# qudong.net
KiCad netlist of a schematic drawn in Altium Designer
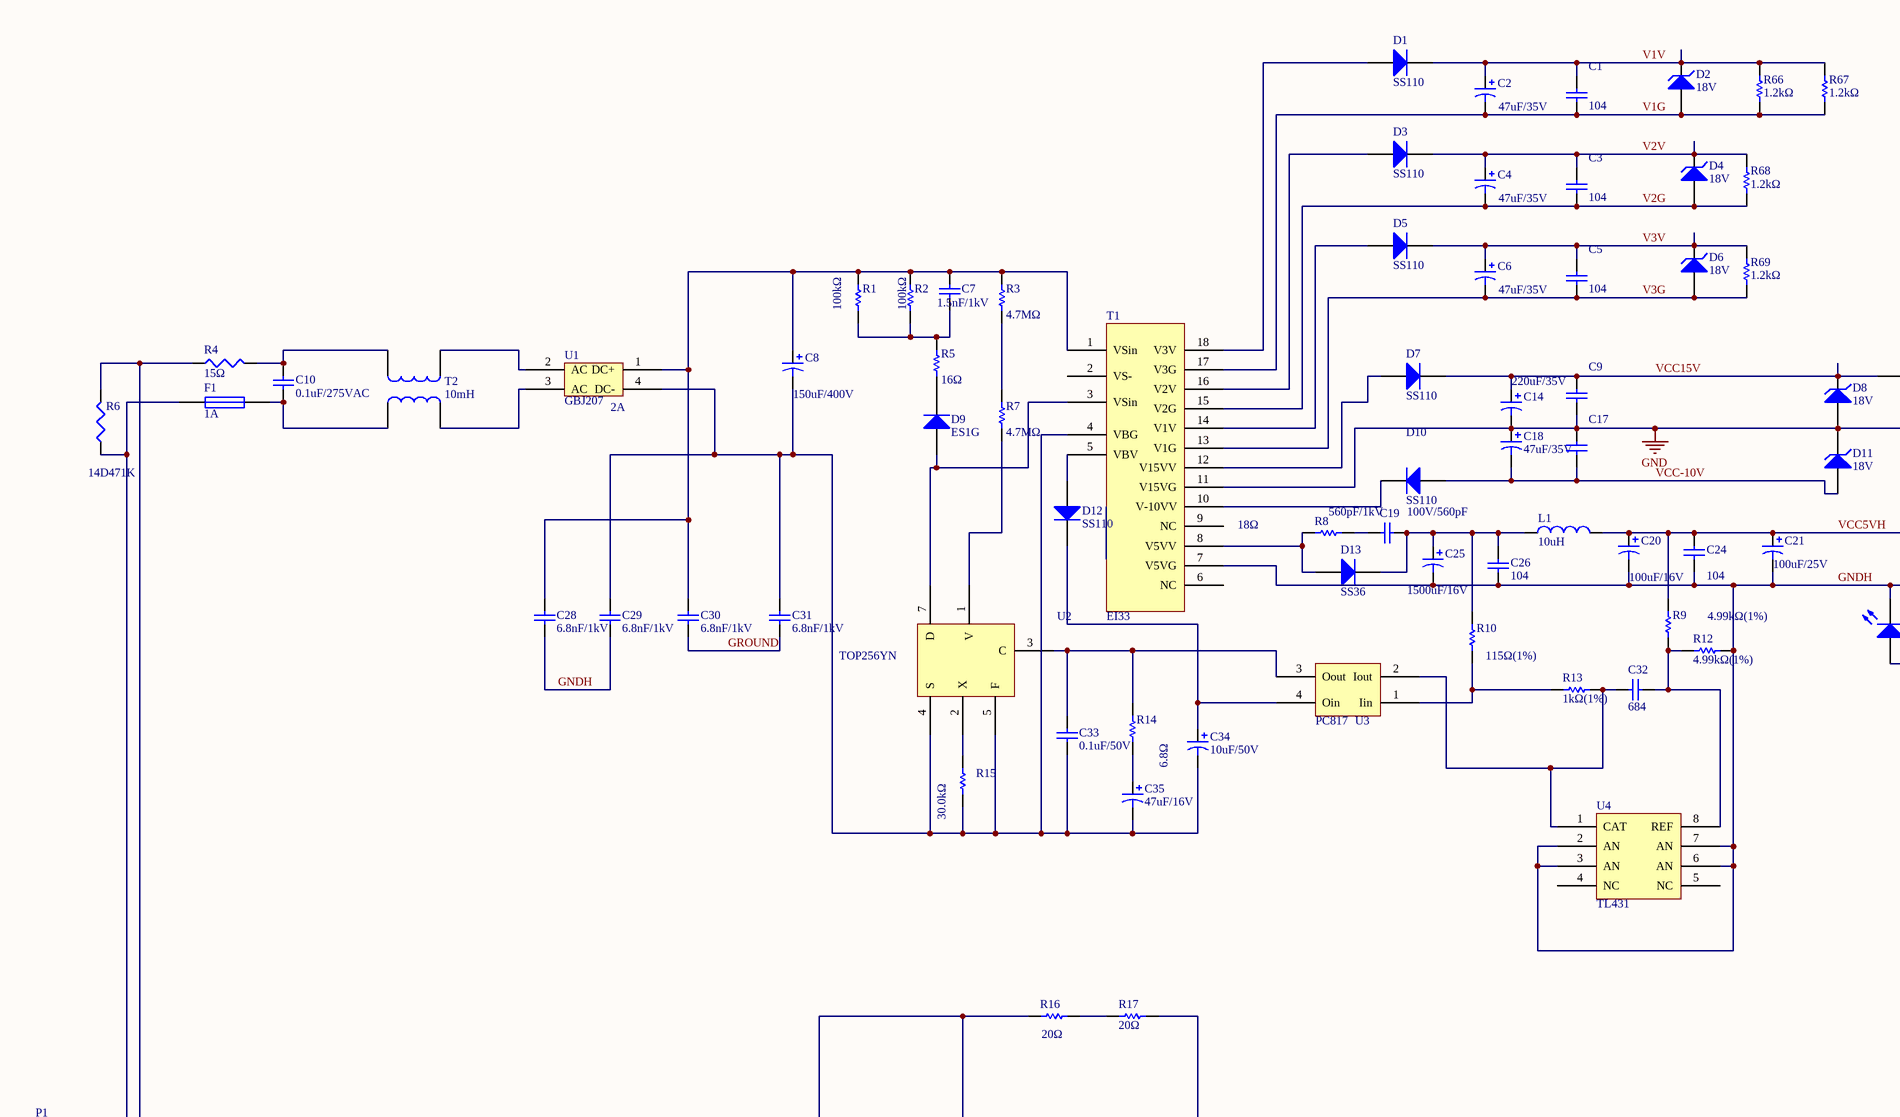
[diagram p0: qudong.SchDoc, top left]
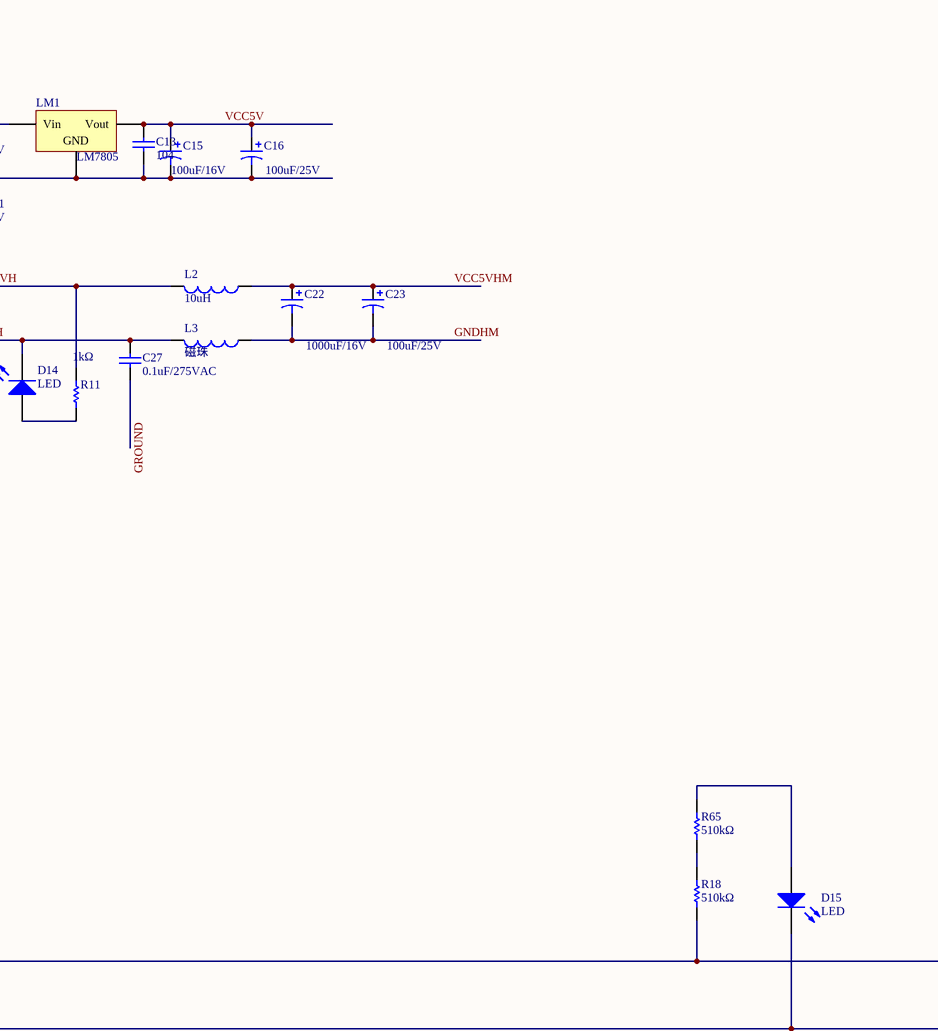
[diagram p1: qudong.SchDoc, top right]
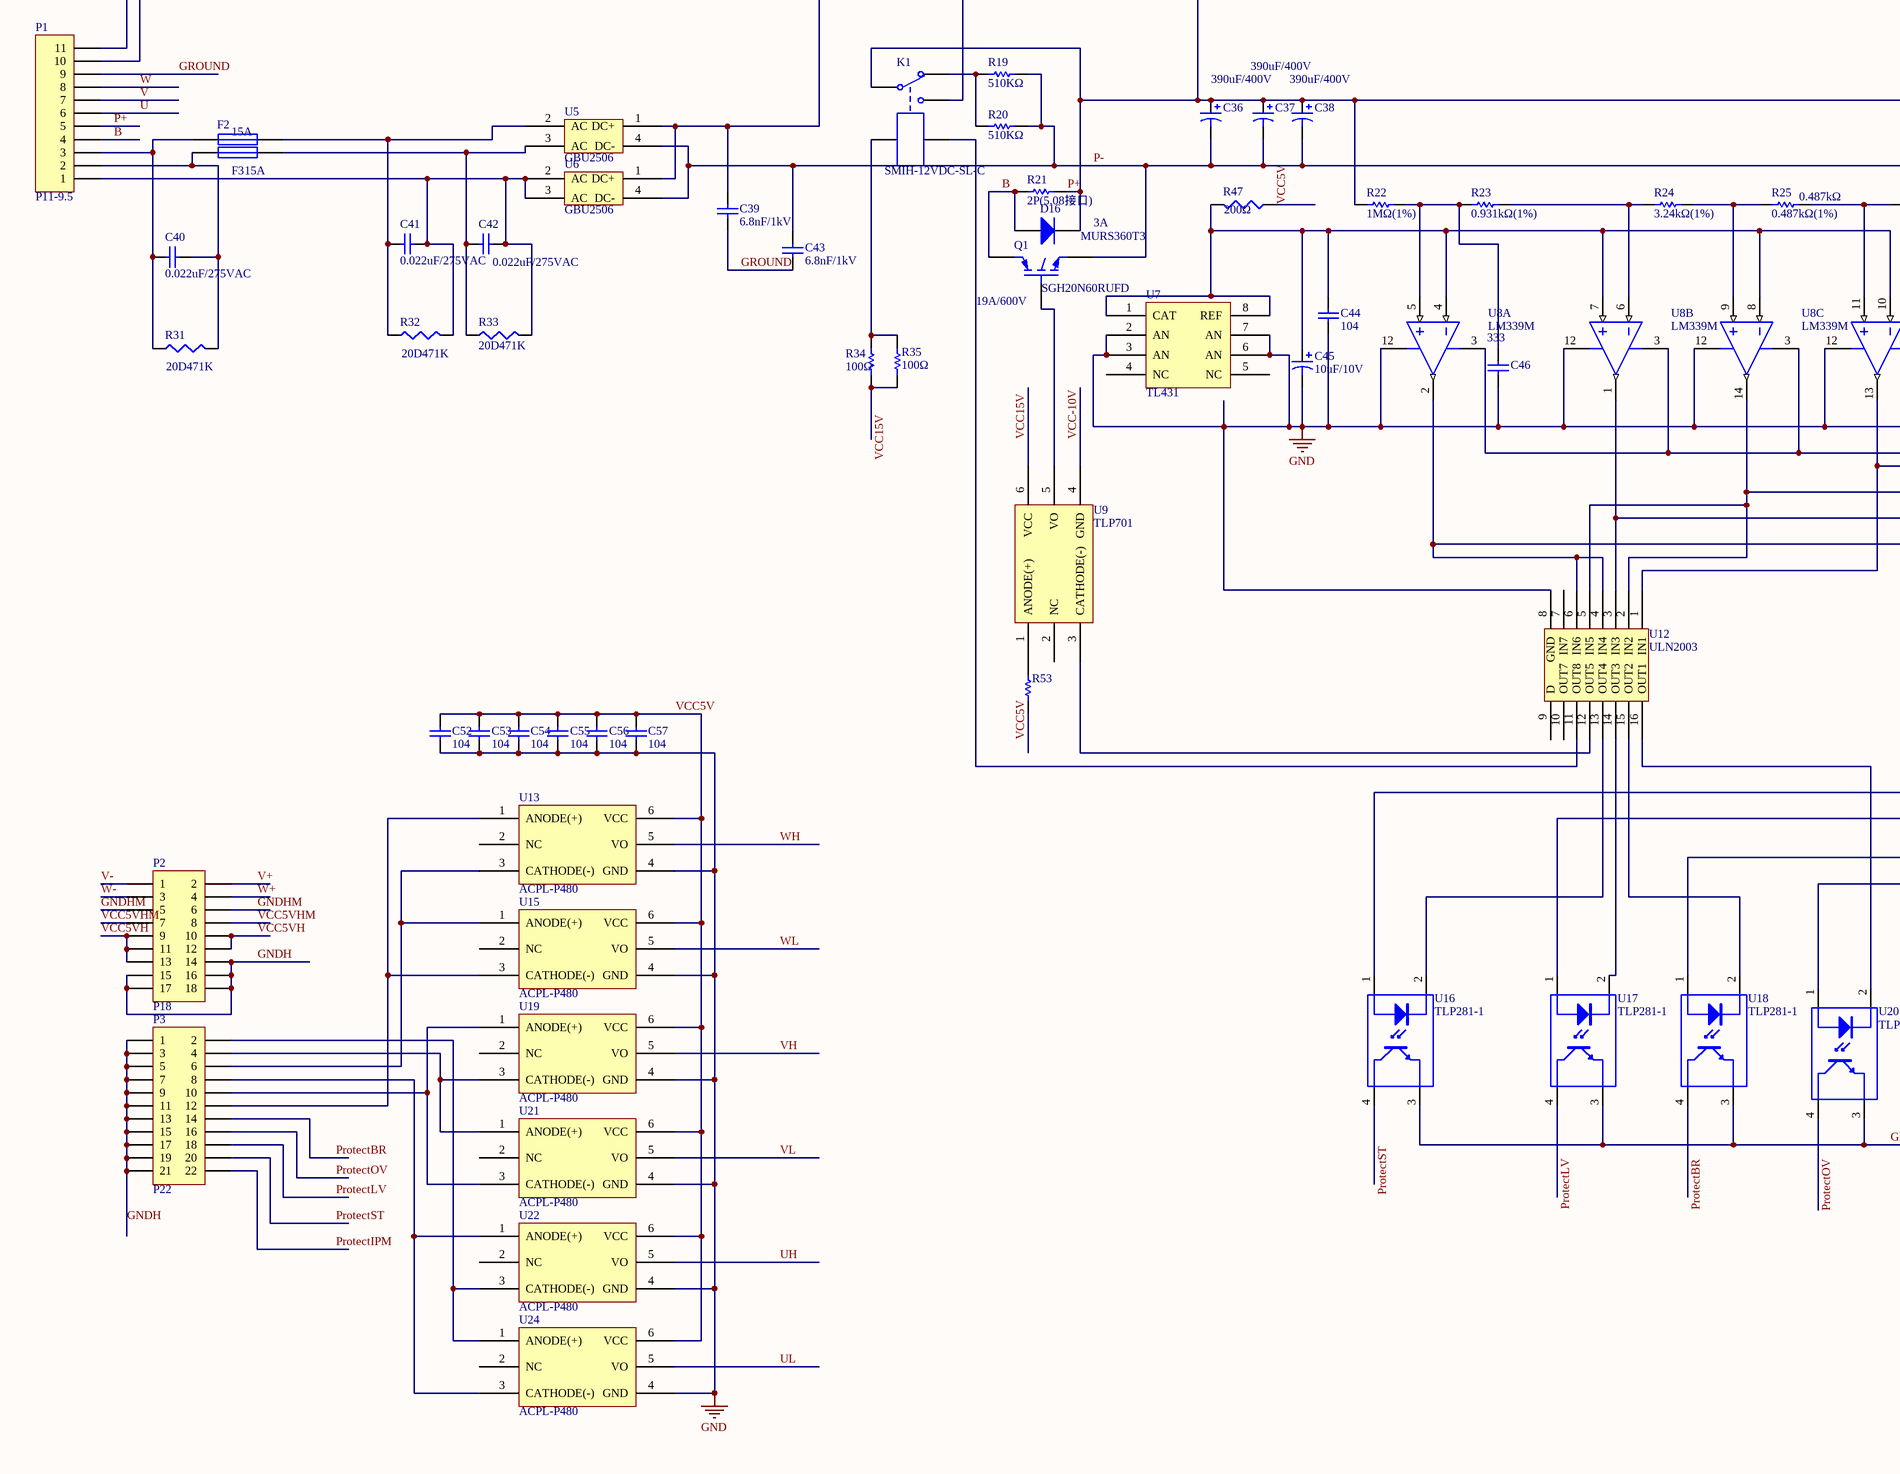
[diagram p2: qudong.SchDoc, bottom left]
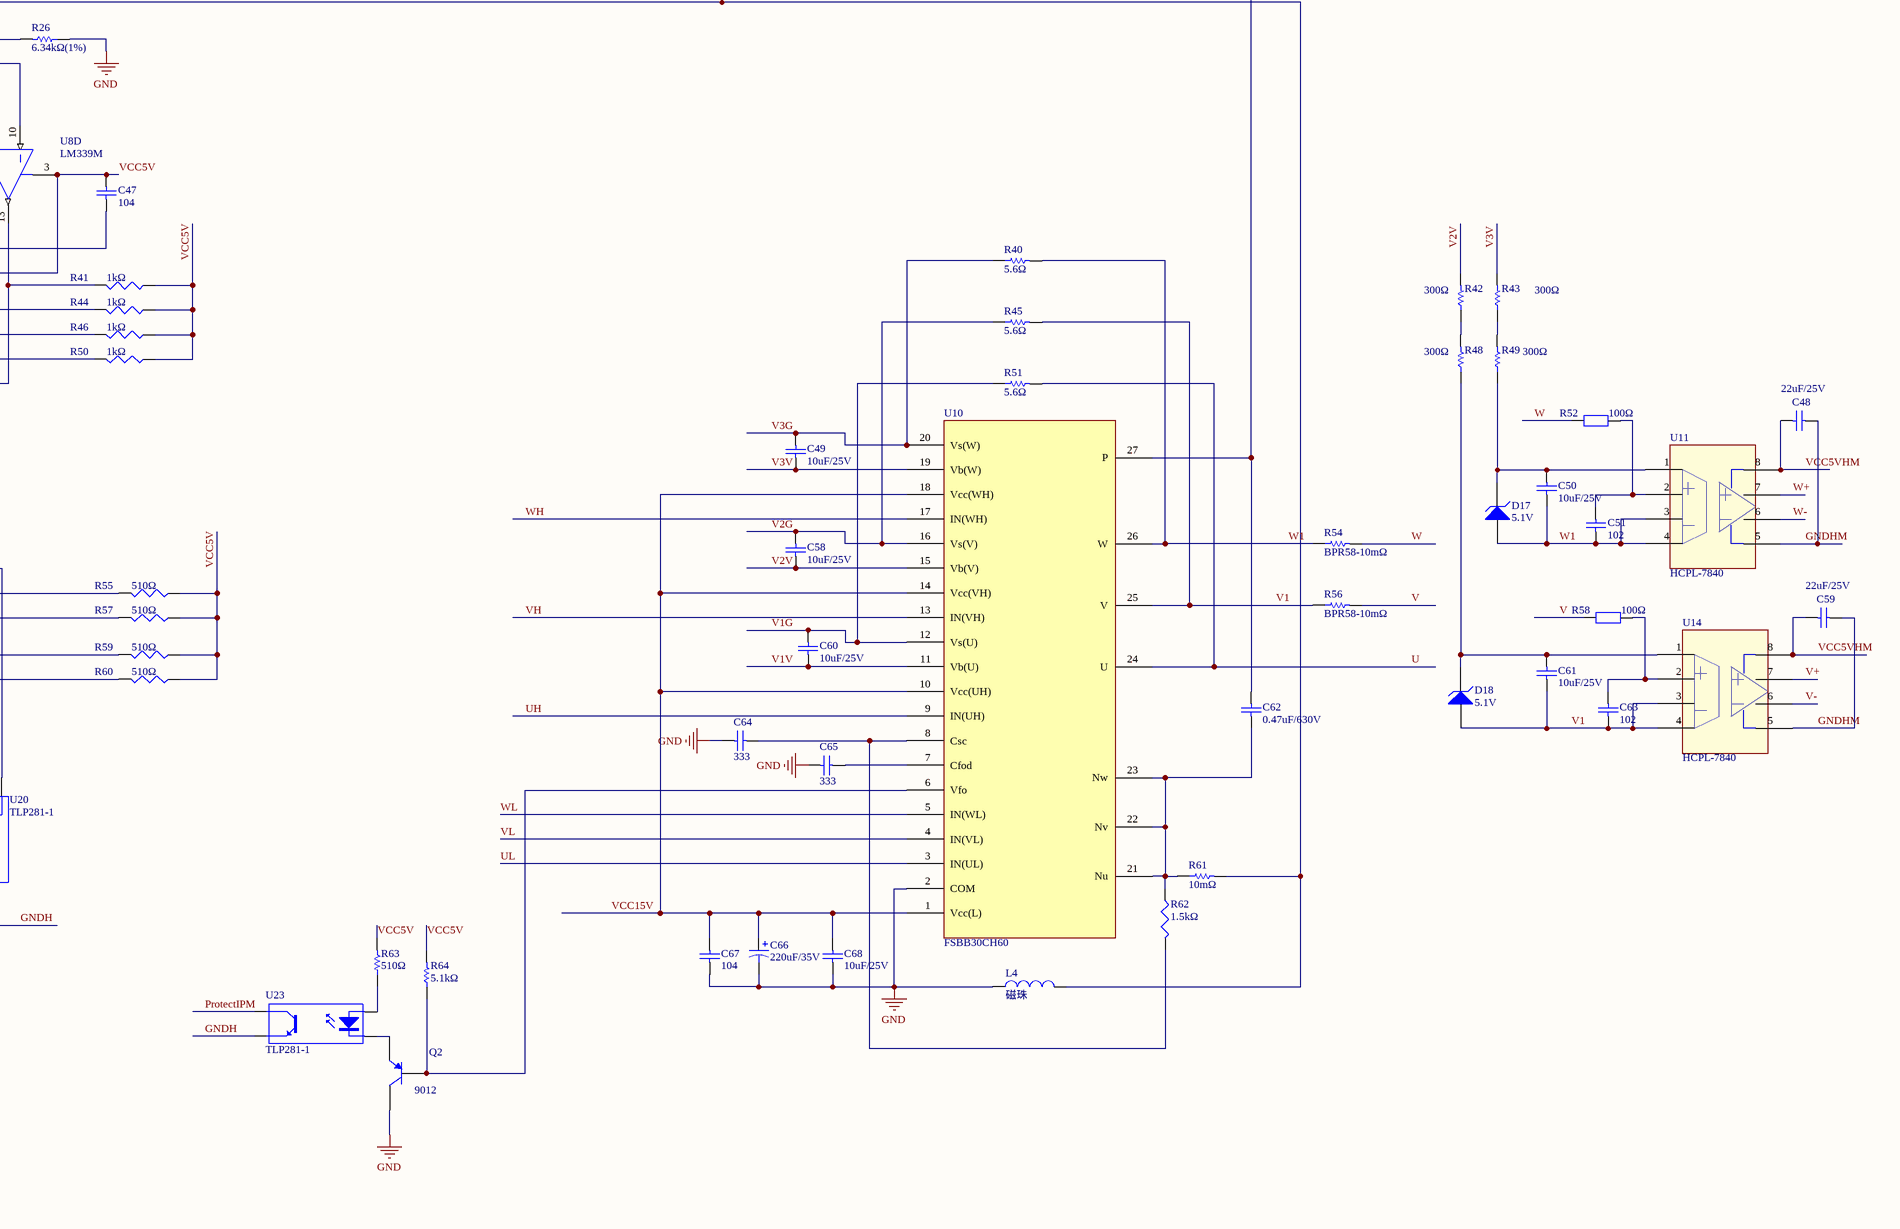
[diagram p3: qudong.SchDoc, bottom right]

(export (version "E")
  (design (tool "Eeschema 10.0.6"))
  (components
    (comp (ref "C1")
      (value "104")
      (footprint "0805C")
      (description "贴片电容0805C")
      (fields (field (name "PUBLISHER") "Altium Limited"))
      (libsource (lib "Miscellaneous Devices") (part "Cap"))
    )
    (comp (ref "C2")
      (value "47uF/35V")
      (footprint "35V/220uF")
      (description "电解电容")
      (fields (field (name "PUBLISHER") "Altium Limited"))
      (libsource (lib "Miscellaneous Devices") (part "Cap Pol1"))
    )
    (comp (ref "C3")
      (value "104")
      (footprint "0805C")
      (description "贴片电容0805C")
      (fields (field (name "PUBLISHER") "Altium Limited"))
      (libsource (lib "Miscellaneous Devices") (part "Cap"))
    )
    (comp (ref "C4")
      (value "47uF/35V")
      (footprint "35V/220uF")
      (description "电解电容")
      (fields (field (name "PUBLISHER") "Altium Limited"))
      (libsource (lib "Miscellaneous Devices") (part "Cap Pol1"))
    )
    (comp (ref "C5")
      (value "104")
      (footprint "0805C")
      (description "贴片电容0805C")
      (fields (field (name "PUBLISHER") "Altium Limited"))
      (libsource (lib "Miscellaneous Devices") (part "Cap"))
    )
    (comp (ref "C6")
      (value "47uF/35V")
      (footprint "35V/220uF")
      (description "电解电容")
      (fields (field (name "PUBLISHER") "Altium Limited"))
      (libsource (lib "Miscellaneous Devices") (part "Cap Pol1"))
    )
    (comp (ref "C7")
      (value "1.5nF/1kV")
      (footprint "RAD-0.2")
      (description "高压瓷片")
      (fields (field (name "PUBLISHER") "Altium Limited"))
      (libsource (lib "Miscellaneous Devices") (part "Cap"))
    )
    (comp (ref "C8")
      (value "150uF/400V")
      (footprint "400V/100uF")
      (description "红宝石电解电容（控制回路主电容）")
      (fields (field (name "PUBLISHER") "Altium Limited"))
      (libsource (lib "Miscellaneous Devices") (part "Cap Pol1"))
    )
    (comp (ref "C9")
      (value "104")
      (footprint "0805C")
      (description "贴片电容0805C")
      (fields (field (name "PUBLISHER") "Altium Limited"))
      (libsource (lib "Miscellaneous Devices") (part "Cap"))
    )
    (comp (ref "C10")
      (value "0.1uF/275VAC")
      (footprint "275AC/0.1F")
      (description "安规电容")
      (fields (field (name "PUBLISHER") "Altium Limited"))
      (libsource (lib "Miscellaneous Devices") (part "Cap"))
    )
    (comp (ref "C13")
      (value "104")
      (footprint "0805C")
      (description "贴片电容0805C")
      (fields (field (name "PUBLISHER") "Altium Limited"))
      (libsource (lib "Miscellaneous Devices") (part "Cap"))
    )
    (comp (ref "C14")
      (value "220uF/35V")
      (footprint "35V/1000uF")
      (description "电解电容")
      (fields (field (name "PUBLISHER") "Altium Limited"))
      (libsource (lib "Miscellaneous Devices") (part "Cap Pol1"))
    )
    (comp (ref "C15")
      (value "100uF/16V")
      (footprint "16V/1000uF")
      (description "电解电容")
      (fields (field (name "PUBLISHER") "Altium Limited"))
      (libsource (lib "Miscellaneous Devices") (part "Cap Pol1"))
    )
    (comp (ref "C16")
      (value "100uF/25V")
      (footprint "7343TAC")
      (description "钽电容")
      (fields (field (name "PUBLISHER") "Altium Limited"))
      (libsource (lib "Miscellaneous Devices") (part "Cap Pol1"))
    )
    (comp (ref "C17")
      (value "104")
      (footprint "0805C")
      (description "贴片电容0805C")
      (fields (field (name "PUBLISHER") "Altium Limited"))
      (libsource (lib "Miscellaneous Devices") (part "Cap"))
    )
    (comp (ref "C18")
      (value "47uF/35V")
      (footprint "35V/220uF")
      (description "电解电容")
      (fields (field (name "PUBLISHER") "Altium Limited"))
      (libsource (lib "Miscellaneous Devices") (part "Cap Pol1"))
    )
    (comp (ref "C19")
      (value "560pF/1kV")
      (footprint "RAD-0.2")
      (description "高压瓷片")
      (fields (field (name "ALTIUM_VALUE") "100V/560pF") (field (name "PUBLISHER") "Altium Limited"))
      (libsource (lib "Miscellaneous Devices") (part "Cap"))
    )
    (comp (ref "C20")
      (value "100uF/16V")
      (footprint "16V/3300uF")
      (description "电解电容")
      (fields (field (name "PUBLISHER") "Altium Limited"))
      (libsource (lib "Miscellaneous Devices") (part "Cap Pol1"))
    )
    (comp (ref "C21")
      (value "100uF/25V")
      (footprint "7343TAC")
      (description "钽电容")
      (fields (field (name "PUBLISHER") "Altium Limited"))
      (libsource (lib "Miscellaneous Devices") (part "Cap Pol1"))
    )
    (comp (ref "C22")
      (value "1000uF/16V")
      (footprint "16V/1000uF")
      (description "电解电容")
      (fields (field (name "PUBLISHER") "Altium Limited"))
      (libsource (lib "Miscellaneous Devices") (part "Cap Pol1"))
    )
    (comp (ref "C23")
      (value "100uF/25V")
      (footprint "7343TAC")
      (description "钽电容")
      (fields (field (name "PUBLISHER") "Altium Limited"))
      (libsource (lib "Miscellaneous Devices") (part "Cap Pol1"))
    )
    (comp (ref "C24")
      (value "104")
      (footprint "0805C")
      (description "贴片电容0805C")
      (fields (field (name "PUBLISHER") "Altium Limited"))
      (libsource (lib "Miscellaneous Devices") (part "Cap"))
    )
    (comp (ref "C25")
      (value "1500uF/16V")
      (footprint "16V/3300uF")
      (description "电解电容")
      (fields (field (name "PUBLISHER") "Altium Limited"))
      (libsource (lib "Miscellaneous Devices") (part "Cap Pol1"))
    )
    (comp (ref "C26")
      (value "104")
      (footprint "0805C")
      (description "贴片电容0805C")
      (fields (field (name "PUBLISHER") "Altium Limited"))
      (libsource (lib "Miscellaneous Devices") (part "Cap"))
    )
    (comp (ref "C27")
      (value "0.1uF/275VAC")
      (footprint "275AC/0.1F")
      (description "安规电容")
      (fields (field (name "PUBLISHER") "Altium Limited"))
      (libsource (lib "Miscellaneous Devices") (part "Cap"))
    )
    (comp (ref "C28")
      (value "6.8nF/1kV")
      (footprint "RAD-0.2")
      (description "高压瓷片")
      (fields (field (name "PUBLISHER") "Altium Limited"))
      (libsource (lib "Miscellaneous Devices") (part "Cap"))
    )
    (comp (ref "C29")
      (value "6.8nF/1kV")
      (footprint "RAD-0.2")
      (description "高压瓷片")
      (fields (field (name "PUBLISHER") "Altium Limited"))
      (libsource (lib "Miscellaneous Devices") (part "Cap"))
    )
    (comp (ref "C30")
      (value "6.8nF/1kV")
      (footprint "RAD-0.2")
      (description "高压瓷片")
      (fields (field (name "PUBLISHER") "Altium Limited"))
      (libsource (lib "Miscellaneous Devices") (part "Cap"))
    )
    (comp (ref "C31")
      (value "6.8nF/1kV")
      (footprint "RAD-0.2")
      (description "高压瓷片")
      (fields (field (name "PUBLISHER") "Altium Limited"))
      (libsource (lib "Miscellaneous Devices") (part "Cap"))
    )
    (comp (ref "C32")
      (value "684")
      (footprint "0805C")
      (description "贴片电容0805C")
      (fields (field (name "PUBLISHER") "Altium Limited"))
      (libsource (lib "Miscellaneous Devices") (part "Cap"))
    )
    (comp (ref "C33")
      (value "0.1uF/50V")
      (footprint "RAD-0.1")
      (description "独石电容")
      (fields (field (name "PUBLISHER") "Altium Limited"))
      (libsource (lib "Miscellaneous Devices") (part "Cap"))
    )
    (comp (ref "C34")
      (value "10uF/50V")
      (footprint "10uF~47uF")
      (description "电解电容")
      (fields (field (name "PUBLISHER") "Altium Limited"))
      (libsource (lib "Miscellaneous Devices") (part "Cap Pol1"))
    )
    (comp (ref "C35")
      (value "47uF/16V")
      (footprint "10uF~47uF")
      (description "电解电容")
      (fields (field (name "PUBLISHER") "Altium Limited"))
      (libsource (lib "Miscellaneous Devices") (part "Cap Pol1"))
    )
    (comp (ref "C36")
      (value "390uF/400V")
      (footprint "C470uF/400V")
      (description "红宝石电解电容（主电容）")
      (fields (field (name "PUBLISHER") "Altium Limited"))
      (libsource (lib "Miscellaneous Devices") (part "Cap Pol1"))
    )
    (comp (ref "C37")
      (value "390uF/400V")
      (footprint "C470uF/400V")
      (description "红宝石电解电容（主电容）")
      (fields (field (name "PUBLISHER") "Altium Limited"))
      (libsource (lib "Miscellaneous Devices") (part "Cap Pol1"))
    )
    (comp (ref "C38")
      (value "390uF/400V")
      (footprint "C470uF/400V")
      (description "红宝石电解电容（主电容）")
      (fields (field (name "PUBLISHER") "Altium Limited"))
      (libsource (lib "Miscellaneous Devices") (part "Cap Pol1"))
    )
    (comp (ref "C39")
      (value "6.8nF/1kV")
      (footprint "RAD-0.2")
      (description "高压瓷片")
      (fields (field (name "PUBLISHER") "Altium Limited"))
      (libsource (lib "Miscellaneous Devices") (part "Cap"))
    )
    (comp (ref "C40")
      (value "0.022uF/275VAC")
      (footprint "275VAC223")
      (description "安规电容")
      (fields (field (name "PUBLISHER") "Altium Limited"))
      (libsource (lib "Miscellaneous Devices") (part "Cap"))
    )
    (comp (ref "C41")
      (value "0.022uF/275VAC")
      (footprint "275VAC223")
      (description "安规电容")
      (fields (field (name "PUBLISHER") "Altium Limited"))
      (libsource (lib "Miscellaneous Devices") (part "Cap"))
    )
    (comp (ref "C42")
      (value "0.022uF/275VAC")
      (footprint "275VAC223")
      (description "安规电容")
      (fields (field (name "PUBLISHER") "Altium Limited"))
      (libsource (lib "Miscellaneous Devices") (part "Cap"))
    )
    (comp (ref "C43")
      (value "6.8nF/1kV")
      (footprint "RAD-0.2")
      (description "高压瓷片")
      (fields (field (name "PUBLISHER") "Altium Limited"))
      (libsource (lib "Miscellaneous Devices") (part "Cap"))
    )
    (comp (ref "C44")
      (value "104")
      (footprint "0805C")
      (description "贴片电容0805C")
      (fields (field (name "PUBLISHER") "Altium Limited"))
      (libsource (lib "Miscellaneous Devices") (part "Cap"))
    )
    (comp (ref "C45")
      (value "10uF/10V")
      (footprint "10uF~47uF")
      (description "电解电容")
      (fields (field (name "PUBLISHER") "Altium Limited"))
      (libsource (lib "Miscellaneous Devices") (part "Cap Pol1"))
    )
    (comp (ref "C46")
      (value "333")
      (footprint "0805C")
      (description "贴片电容0805C")
      (fields (field (name "PUBLISHER") "Altium Limited"))
      (libsource (lib "Miscellaneous Devices") (part "Cap"))
    )
    (comp (ref "C47")
      (value "104")
      (footprint "0805C")
      (description "贴片电容0805C")
      (fields (field (name "PUBLISHER") "Altium Limited"))
      (libsource (lib "Miscellaneous Devices") (part "Cap"))
    )
    (comp (ref "C48")
      (value "22uF/25V")
      (footprint "1812C")
      (description "贴片电容1812C")
      (fields (field (name "PUBLISHER") "Altium Limited"))
      (libsource (lib "Miscellaneous Devices") (part "Cap"))
    )
    (comp (ref "C49")
      (value "10uF/25V")
      (footprint "1210C")
      (description "贴片电容1210C")
      (fields (field (name "PUBLISHER") "Altium Limited"))
      (libsource (lib "Miscellaneous Devices") (part "Cap"))
    )
    (comp (ref "C50")
      (value "10uF/25V")
      (footprint "1210C")
      (description "贴片电容1210C")
      (fields (field (name "PUBLISHER") "Altium Limited"))
      (libsource (lib "Miscellaneous Devices") (part "Cap"))
    )
    (comp (ref "C51")
      (value "102")
      (footprint "0805C")
      (description "贴片电容0805C")
      (fields (field (name "PUBLISHER") "Altium Limited"))
      (libsource (lib "Miscellaneous Devices") (part "Cap"))
    )
    (comp (ref "C52")
      (value "104")
      (footprint "0805C")
      (description "贴片电容0805C")
      (fields (field (name "PUBLISHER") "Altium Limited"))
      (libsource (lib "Miscellaneous Devices") (part "Cap"))
    )
    (comp (ref "C53")
      (value "104")
      (footprint "0805C")
      (description "贴片电容0805C")
      (fields (field (name "PUBLISHER") "Altium Limited"))
      (libsource (lib "Miscellaneous Devices") (part "Cap"))
    )
    (comp (ref "C54")
      (value "104")
      (footprint "0805C")
      (description "贴片电容0805C")
      (fields (field (name "PUBLISHER") "Altium Limited"))
      (libsource (lib "Miscellaneous Devices") (part "Cap"))
    )
    (comp (ref "C55")
      (value "104")
      (footprint "0805C")
      (description "贴片电容0805C")
      (fields (field (name "PUBLISHER") "Altium Limited"))
      (libsource (lib "Miscellaneous Devices") (part "Cap"))
    )
    (comp (ref "C56")
      (value "104")
      (footprint "0805C")
      (description "贴片电容0805C")
      (fields (field (name "PUBLISHER") "Altium Limited"))
      (libsource (lib "Miscellaneous Devices") (part "Cap"))
    )
    (comp (ref "C57")
      (value "104")
      (footprint "0805C")
      (description "贴片电容0805C")
      (fields (field (name "PUBLISHER") "Altium Limited"))
      (libsource (lib "Miscellaneous Devices") (part "Cap"))
    )
    (comp (ref "C58")
      (value "10uF/25V")
      (footprint "1210C")
      (description "贴片电容1210C")
      (fields (field (name "PUBLISHER") "Altium Limited"))
      (libsource (lib "Miscellaneous Devices") (part "Cap"))
    )
    (comp (ref "C59")
      (value "22uF/25V")
      (footprint "1812C")
      (description "贴片电容1812C")
      (fields (field (name "PUBLISHER") "Altium Limited"))
      (libsource (lib "Miscellaneous Devices") (part "Cap"))
    )
    (comp (ref "C60")
      (value "10uF/25V")
      (footprint "1210C")
      (description "贴片电容1210C")
      (fields (field (name "PUBLISHER") "Altium Limited"))
      (libsource (lib "Miscellaneous Devices") (part "Cap"))
    )
    (comp (ref "C61")
      (value "10uF/25V")
      (footprint "1210C")
      (description "贴片电容1210C")
      (fields (field (name "PUBLISHER") "Altium Limited"))
      (libsource (lib "Miscellaneous Devices") (part "Cap"))
    )
    (comp (ref "C62")
      (value "0.47uF/630V")
      (footprint "474/630V")
      (description "聚苯电容（CBB）")
      (fields (field (name "PUBLISHER") "Altium Limited"))
      (libsource (lib "Miscellaneous Devices") (part "Cap"))
    )
    (comp (ref "C63")
      (value "102")
      (footprint "0805C")
      (description "贴片电容0805C")
      (fields (field (name "PUBLISHER") "Altium Limited"))
      (libsource (lib "Miscellaneous Devices") (part "Cap"))
    )
    (comp (ref "C64")
      (value "333")
      (footprint "0805C")
      (description "贴片电容0805C")
      (fields (field (name "PUBLISHER") "Altium Limited"))
      (libsource (lib "Miscellaneous Devices") (part "Cap"))
    )
    (comp (ref "C65")
      (value "333")
      (footprint "0805C")
      (description "贴片电容0805C")
      (fields (field (name "PUBLISHER") "Altium Limited"))
      (libsource (lib "Miscellaneous Devices") (part "Cap"))
    )
    (comp (ref "C66")
      (value "220uF/35V")
      (footprint "35V/220uF")
      (description "电解电容")
      (fields (field (name "PUBLISHER") "Altium Limited"))
      (libsource (lib "Miscellaneous Devices") (part "Cap Pol1"))
    )
    (comp (ref "C67")
      (value "104")
      (footprint "0805C")
      (description "贴片电容0805C")
      (fields (field (name "PUBLISHER") "Altium Limited"))
      (libsource (lib "Miscellaneous Devices") (part "Cap"))
    )
    (comp (ref "C68")
      (value "10uF/25V")
      (footprint "1210C")
      (description "贴片电容1210C")
      (fields (field (name "PUBLISHER") "Altium Limited"))
      (libsource (lib "Miscellaneous Devices") (part "Cap"))
    )
    (comp (ref "D1")
      (value "SS110")
      (footprint "DO214")
      (description "ES1G")
      (fields (field (name "PUBLISHER") "Altium Limited"))
      (libsource (lib "Miscellaneous Devices") (part "Diode"))
    )
    (comp (ref "D2")
      (value "18V")
      (footprint "DO214")
      (description "稳压管")
      (fields (field (name "PUBLISHER") "Altium Limited"))
      (libsource (lib "Miscellaneous Devices") (part "D Zener"))
    )
    (comp (ref "D3")
      (value "SS110")
      (footprint "DO214")
      (description "ES1G")
      (fields (field (name "PUBLISHER") "Altium Limited"))
      (libsource (lib "Miscellaneous Devices") (part "Diode"))
    )
    (comp (ref "D4")
      (value "18V")
      (footprint "DO214")
      (description "稳压管")
      (fields (field (name "PUBLISHER") "Altium Limited"))
      (libsource (lib "Miscellaneous Devices") (part "D Zener"))
    )
    (comp (ref "D5")
      (value "SS110")
      (footprint "DO214")
      (description "ES1G")
      (fields (field (name "PUBLISHER") "Altium Limited"))
      (libsource (lib "Miscellaneous Devices") (part "Diode"))
    )
    (comp (ref "D6")
      (value "18V")
      (footprint "DO214")
      (description "稳压管")
      (fields (field (name "PUBLISHER") "Altium Limited"))
      (libsource (lib "Miscellaneous Devices") (part "D Zener"))
    )
    (comp (ref "D7")
      (value "SS110")
      (footprint "DO214")
      (description "ES1G")
      (fields (field (name "PUBLISHER") "Altium Limited"))
      (libsource (lib "Miscellaneous Devices") (part "Diode"))
    )
    (comp (ref "D8")
      (value "18V")
      (footprint "DO214")
      (description "稳压管")
      (fields (field (name "PUBLISHER") "Altium Limited"))
      (libsource (lib "Miscellaneous Devices") (part "D Zener"))
    )
    (comp (ref "D9")
      (value "ES1G")
      (footprint "DO214")
      (fields (field (name "PUBLISHER") "Altium Limited"))
      (libsource (lib "Miscellaneous Devices") (part "Diode"))
    )
    (comp (ref "D10")
      (value "SS110")
      (footprint "DO214")
      (description "ES1G")
      (fields (field (name "PUBLISHER") "Altium Limited"))
      (libsource (lib "Miscellaneous Devices") (part "Diode"))
    )
    (comp (ref "D11")
      (value "18V")
      (footprint "DO214")
      (description "稳压管")
      (fields (field (name "PUBLISHER") "Altium Limited"))
      (libsource (lib "Miscellaneous Devices") (part "D Zener"))
    )
    (comp (ref "D12")
      (value "SS110")
      (footprint "DO214")
      (description "ES1G")
      (fields (field (name "PUBLISHER") "Altium Limited"))
      (libsource (lib "Miscellaneous Devices") (part "Diode"))
    )
    (comp (ref "D13")
      (value "SS36")
      (footprint "MURS360T3")
      (description "ES3B")
      (fields (field (name "PUBLISHER") "Altium Limited"))
      (libsource (lib "Miscellaneous Devices") (part "Diode"))
    )
    (comp (ref "D14")
      (value "LED")
      (footprint "0805D")
      (description "发光二极管")
      (fields (field (name "PUBLISHER") "Altium Limited"))
      (libsource (lib "Miscellaneous Devices") (part "LED1"))
    )
    (comp (ref "D15")
      (value "LED")
      (footprint "0805D")
      (description "发光二极管")
      (fields (field (name "PUBLISHER") "Altium Limited"))
      (libsource (lib "Miscellaneous Devices") (part "LED1"))
    )
    (comp (ref "D16")
      (value "MURS360T3")
      (footprint "MURS360T3")
      (fields (field (name "ALTIUM_VALUE") "3A") (field (name "PUBLISHER") "Altium Limited"))
      (libsource (lib "Miscellaneous Devices") (part "Diode"))
    )
    (comp (ref "D17")
      (value "5.1V")
      (footprint "DO214")
      (description "稳压管")
      (fields (field (name "PUBLISHER") "Altium Limited"))
      (libsource (lib "Miscellaneous Devices") (part "D Zener"))
    )
    (comp (ref "D18")
      (value "5.1V")
      (footprint "DO214")
      (description "稳压管")
      (fields (field (name "PUBLISHER") "Altium Limited"))
      (libsource (lib "Miscellaneous Devices") (part "D Zener"))
    )
    (comp (ref "F1")
      (value "1A")
      (footprint "Fusesmall")
      (description "保险丝圆形")
      (fields (field (name "PUBLISHER") "Altium Limited"))
      (libsource (lib "Miscellaneous Devices") (part "Fuse 1"))
    )
    (comp (ref "F2")
      (value "15A")
      (footprint "FUSH_2cm")
      (description "保险丝25mm")
      (fields (field (name "PUBLISHER") "Altium Limited"))
      (libsource (lib "Miscellaneous Devices") (part "Fuse 1"))
    )
    (comp (ref "F3")
      (value "15A")
      (footprint "FUSH_2cm")
      (description "保险丝25mm")
      (fields (field (name "PUBLISHER") "Altium Limited"))
      (libsource (lib "Miscellaneous Devices") (part "Fuse 1"))
    )
    (comp (ref "K1")
      (value "SMIH-12VDC-SL-C")
      (footprint "SMIH-12VDC-SL-C")
      (description "继电器")
      (fields (field (name "PUBLISHER") "Altium Limited"))
      (libsource (lib "Miscellaneous Devices") (part "Relay-SPDT"))
    )
    (comp (ref "L1")
      (value "10uH")
      (footprint "L4.7uH")
      (description "工字电感")
      (fields (field (name "PUBLISHER") "Altium Limited"))
      (libsource (lib "qudong_1") (part "Inductor"))
    )
    (comp (ref "L2")
      (value "10uH")
      (footprint "L4.7uH")
      (description "工字电感")
      (fields (field (name "PUBLISHER") "Altium Limited"))
      (libsource (lib "qudong_1") (part "Inductor"))
    )
    (comp (ref "L3")
      (value "磁珠")
      (footprint "AXIAL-0.4")
      (fields (field (name "PUBLISHER") "Altium Limited"))
      (libsource (lib "qudong_1") (part "Inductor"))
    )
    (comp (ref "L4")
      (value "磁珠")
      (footprint "AXIAL-0.4")
      (fields (field (name "PUBLISHER") "Altium Limited"))
      (libsource (lib "qudong_1") (part "Inductor"))
    )
    (comp (ref "LM1")
      (value "LM7805")
      (footprint "LD1085")
      (fields (field (name "PUBLISHER") "Altium Limited"))
      (libsource (lib "Miscellaneous Devices") (part "Volt Reg"))
    )
    (comp (ref "P1")
      (value "P11-9.5")
      (footprint "P11")
      (description "45R-9.5mm-11P(主接口)")
      (fields (field (name "PUBLISHER") "Altium Limited"))
      (libsource (lib "Miscellaneous Connectors") (part "Header 11"))
    )
    (comp (ref "P2")
      (value "P18")
      (footprint "FFC_1.0mm_18pin_直")
      (description "电源接口（软排线）")
      (fields (field (name "PUBLISHER") "Altium Limited"))
      (libsource (lib "Miscellaneous Connectors") (part "Header 9X2"))
    )
    (comp (ref "P3")
      (value "P22")
      (footprint "FFC_1.0mm_22pin_直")
      (description "数字接口（软排线）")
      (fields (field (name "PUBLISHER") "Altium Limited"))
      (libsource (lib "Miscellaneous Connectors") (part "Header 11X2"))
    )
    (comp (ref "Q1")
      (value "SGH20N60RUFD")
      (footprint "SFM-F3/Y2.3")
      (fields (field (name "ALTIUM_VALUE") "19A/600V") (field (name "PUBLISHER") "Altium Limited"))
      (libsource (lib "Miscellaneous Devices") (part "IGBT-N"))
    )
    (comp (ref "Q2")
      (value "9012")
      (footprint "SOT23")
      (description "贴片三极管PNP")
      (fields (field (name "PUBLISHER") "Altium Limited"))
      (libsource (lib "Miscellaneous Devices") (part "2N3906"))
    )
    (comp (ref "R1")
      (value "100kΩ")
      (footprint "R_2W")
      (description "2W直插碳膜电阻")
      (fields (field (name "PUBLISHER") "Altium Limited"))
      (libsource (lib "Miscellaneous Devices") (part "Res1"))
    )
    (comp (ref "R2")
      (value "100kΩ")
      (footprint "R_2W")
      (description "2W直插碳膜电阻")
      (fields (field (name "PUBLISHER") "Altium Limited"))
      (libsource (lib "Miscellaneous Devices") (part "Res1"))
    )
    (comp (ref "R3")
      (value "4.7MΩ")
      (footprint "1206R")
      (description "贴片电阻1206R")
      (fields (field (name "Comment") "2MΩ") (field (name "PUBLISHER") "Altium Limited"))
      (libsource (lib "Miscellaneous Devices") (part "Res1"))
    )
    (comp (ref "R4")
      (value "15Ω")
      (footprint "AXIAL-0.3")
      (description "热敏电阻")
      (fields (field (name "PUBLISHER") "Altium Limited"))
      (libsource (lib "Miscellaneous Devices") (part "Res3"))
    )
    (comp (ref "R5")
      (value "16Ω")
      (footprint "1206R")
      (description "贴片电阻1206R")
      (fields (field (name "PUBLISHER") "Altium Limited"))
      (libsource (lib "Miscellaneous Devices") (part "Res1"))
    )
    (comp (ref "R6")
      (value "14D471K")
      (footprint "14D471K")
      (description "压敏电阻")
      (fields (field (name "PUBLISHER") "Altium Limited"))
      (libsource (lib "Miscellaneous Devices") (part "Res3"))
    )
    (comp (ref "R7")
      (value "4.7MΩ")
      (footprint "1206R")
      (description "贴片电阻1206R")
      (fields (field (name "Comment") "2MΩ") (field (name "PUBLISHER") "Altium Limited"))
      (libsource (lib "Miscellaneous Devices") (part "Res1"))
    )
    (comp (ref "R8")
      (value "18Ω")
      (footprint "1206R")
      (description "贴片电阻1206R")
      (fields (field (name "PUBLISHER") "Altium Limited"))
      (libsource (lib "Miscellaneous Devices") (part "Res1"))
    )
    (comp (ref "R9")
      (value "4.99kΩ(1%)")
      (footprint "0805R1%")
      (description "贴片电阻0805R（1%）")
      (fields (field (name "PUBLISHER") "Altium Limited"))
      (libsource (lib "Miscellaneous Devices") (part "Res1"))
    )
    (comp (ref "R10")
      (value "115Ω(1%)")
      (footprint "0805R1%")
      (description "贴片电阻0805R（1%）")
      (fields (field (name "PUBLISHER") "Altium Limited"))
      (libsource (lib "Miscellaneous Devices") (part "Res1"))
    )
    (comp (ref "R11")
      (value "1kΩ")
      (footprint "0805R")
      (description "贴片电阻0805R")
      (fields (field (name "PUBLISHER") "Altium Limited"))
      (libsource (lib "Miscellaneous Devices") (part "Res1"))
    )
    (comp (ref "R12")
      (value "4.99kΩ(1%)")
      (footprint "0805R1%")
      (description "贴片电阻0805R（1%）")
      (fields (field (name "PUBLISHER") "Altium Limited"))
      (libsource (lib "Miscellaneous Devices") (part "Res1"))
    )
    (comp (ref "R13")
      (value "1kΩ(1%)")
      (footprint "0805R1%")
      (description "贴片电阻0805R（1%）")
      (fields (field (name "PUBLISHER") "Altium Limited"))
      (libsource (lib "Miscellaneous Devices") (part "Res1"))
    )
    (comp (ref "R14")
      (value "6.8Ω")
      (footprint "0805R")
      (description "贴片电阻0805R")
      (fields (field (name "PUBLISHER") "Altium Limited"))
      (libsource (lib "Miscellaneous Devices") (part "Res1"))
    )
    (comp (ref "R15")
      (value "30.0kΩ")
      (footprint "0805R")
      (description "贴片电阻0805R")
      (fields (field (name "PUBLISHER") "Altium Limited"))
      (libsource (lib "Miscellaneous Devices") (part "Res1"))
    )
    (comp (ref "R16")
      (value "20Ω")
      (footprint "remindianzu")
      (description "热敏电阻")
      (fields (field (name "PUBLISHER") "Altium Limited"))
      (libsource (lib "Miscellaneous Devices") (part "Res1"))
    )
    (comp (ref "R17")
      (value "20Ω")
      (footprint "remindianzu")
      (description "热敏电阻")
      (fields (field (name "PUBLISHER") "Altium Limited"))
      (libsource (lib "Miscellaneous Devices") (part "Res1"))
    )
    (comp (ref "R18")
      (value "510kΩ")
      (footprint "2010R")
      (description "贴片电阻2010R")
      (fields (field (name "PUBLISHER") "Altium Limited"))
      (libsource (lib "Miscellaneous Devices") (part "Res1"))
    )
    (comp (ref "R19")
      (value "510KΩ")
      (footprint "R0.9")
      (description "3W直插碳膜电阻")
      (fields (field (name "PUBLISHER") "Altium Limited"))
      (libsource (lib "Miscellaneous Devices") (part "Res1"))
    )
    (comp (ref "R20")
      (value "510KΩ")
      (footprint "R0.9")
      (description "3W直插碳膜电阻")
      (fields (field (name "PUBLISHER") "Altium Limited"))
      (libsource (lib "Miscellaneous Devices") (part "Res1"))
    )
    (comp (ref "R21")
      (value "2P(5.08接口)")
      (footprint "2pz")
      (description "KF128绿端5.08-2P直")
      (fields (field (name "PUBLISHER") "Altium Limited"))
      (libsource (lib "Miscellaneous Devices") (part "Res1"))
    )
    (comp (ref "R22")
      (value "1MΩ(1%)")
      (footprint "R0.9")
      (description "3W直插金属膜电阻（1%）")
      (fields (field (name "PUBLISHER") "Altium Limited"))
      (libsource (lib "Miscellaneous Devices") (part "Res1"))
    )
    (comp (ref "R23")
      (value "0.931kΩ(1%)")
      (footprint "0805R1%")
      (description "贴片电阻0805R（1%）")
      (fields (field (name "PUBLISHER") "Altium Limited"))
      (libsource (lib "Miscellaneous Devices") (part "Res1"))
    )
    (comp (ref "R24")
      (value "3.24kΩ(1%)")
      (footprint "0805R1%")
      (description "贴片电阻0805R（1%）")
      (fields (field (name "PUBLISHER") "Altium Limited"))
      (libsource (lib "Miscellaneous Devices") (part "Res1"))
    )
    (comp (ref "R25")
      (value "0.487kΩ(1%)")
      (footprint "0805R1%")
      (description "贴片电阻0805R（1%）")
      (fields (field (name "ALTIUM_VALUE") "0.487kΩ") (field (name "PUBLISHER") "Altium Limited"))
      (libsource (lib "Miscellaneous Devices") (part "Res1"))
    )
    (comp (ref "R26")
      (value "6.34kΩ(1%)")
      (footprint "0805R1%")
      (description "贴片电阻0805R（1%）")
      (fields (field (name "PUBLISHER") "Altium Limited"))
      (libsource (lib "Miscellaneous Devices") (part "Res1"))
    )
    (comp (ref "R31")
      (value "20D471K")
      (footprint "14D471K")
      (description "压敏电阻")
      (fields (field (name "PUBLISHER") "Altium Limited"))
      (libsource (lib "Miscellaneous Devices") (part "Res3"))
    )
    (comp (ref "R32")
      (value "20D471K")
      (footprint "14D471K")
      (description "压敏电阻")
      (fields (field (name "PUBLISHER") "Altium Limited"))
      (libsource (lib "Miscellaneous Devices") (part "Res3"))
    )
    (comp (ref "R33")
      (value "20D471K")
      (footprint "14D471K")
      (description "压敏电阻")
      (fields (field (name "PUBLISHER") "Altium Limited"))
      (libsource (lib "Miscellaneous Devices") (part "Res3"))
    )
    (comp (ref "R34")
      (value "100Ω")
      (footprint "1206R")
      (description "贴片电阻1206R")
      (fields (field (name "PUBLISHER") "Altium Limited"))
      (libsource (lib "Miscellaneous Devices") (part "Res1"))
    )
    (comp (ref "R35")
      (value "100Ω")
      (footprint "1206R")
      (description "贴片电阻1206R")
      (fields (field (name "PUBLISHER") "Altium Limited"))
      (libsource (lib "Miscellaneous Devices") (part "Res1"))
    )
    (comp (ref "R40")
      (value "5.6Ω")
      (footprint "1206R")
      (description "贴片电阻1206R")
      (fields (field (name "PUBLISHER") "Altium Limited"))
      (libsource (lib "Miscellaneous Devices") (part "Res1"))
    )
    (comp (ref "R41")
      (value "1kΩ")
      (footprint "0805R")
      (description "贴片电阻0805R")
      (fields (field (name "PUBLISHER") "Altium Limited"))
      (libsource (lib "Miscellaneous Devices") (part "Res3"))
    )
    (comp (ref "R42")
      (value "300Ω")
      (footprint "1206R")
      (description "贴片电阻1206R")
      (fields (field (name "PUBLISHER") "Altium Limited"))
      (libsource (lib "Miscellaneous Devices") (part "Res1"))
    )
    (comp (ref "R43")
      (value "300Ω")
      (footprint "1206R")
      (description "贴片电阻1206R")
      (fields (field (name "PUBLISHER") "Altium Limited"))
      (libsource (lib "Miscellaneous Devices") (part "Res1"))
    )
    (comp (ref "R44")
      (value "1kΩ")
      (footprint "0805R")
      (description "贴片电阻0805R")
      (fields (field (name "PUBLISHER") "Altium Limited"))
      (libsource (lib "Miscellaneous Devices") (part "Res3"))
    )
    (comp (ref "R45")
      (value "5.6Ω")
      (footprint "1206R")
      (description "贴片电阻1206R")
      (fields (field (name "PUBLISHER") "Altium Limited"))
      (libsource (lib "Miscellaneous Devices") (part "Res1"))
    )
    (comp (ref "R46")
      (value "1kΩ")
      (footprint "0805R")
      (description "贴片电阻0805R")
      (fields (field (name "PUBLISHER") "Altium Limited"))
      (libsource (lib "Miscellaneous Devices") (part "Res3"))
    )
    (comp (ref "R47")
      (value "200Ω")
      (footprint "1206R")
      (description "贴片电阻1206R")
      (fields (field (name "PUBLISHER") "Altium Limited"))
      (libsource (lib "Miscellaneous Devices") (part "Res3"))
    )
    (comp (ref "R48")
      (value "300Ω")
      (footprint "1206R")
      (description "贴片电阻1206R")
      (fields (field (name "PUBLISHER") "Altium Limited"))
      (libsource (lib "Miscellaneous Devices") (part "Res1"))
    )
    (comp (ref "R49")
      (value "300Ω")
      (footprint "1206R")
      (description "贴片电阻1206R")
      (fields (field (name "PUBLISHER") "Altium Limited"))
      (libsource (lib "Miscellaneous Devices") (part "Res1"))
    )
    (comp (ref "R50")
      (value "1kΩ")
      (footprint "0805R")
      (description "贴片电阻0805R")
      (fields (field (name "PUBLISHER") "Altium Limited"))
      (libsource (lib "Miscellaneous Devices") (part "Res3"))
    )
    (comp (ref "R51")
      (value "5.6Ω")
      (footprint "1206R")
      (description "贴片电阻1206R")
      (fields (field (name "PUBLISHER") "Altium Limited"))
      (libsource (lib "Miscellaneous Devices") (part "Res1"))
    )
    (comp (ref "R52")
      (value "100Ω")
      (footprint "0805R")
      (description "贴片电阻0805R")
      (fields (field (name "PUBLISHER") "Altium Limited"))
      (libsource (lib "Miscellaneous Devices") (part "Res2"))
    )
    (comp (ref "R53")
      (value "510Ω")
      (footprint "1206R")
      (description "贴片电阻1206R")
      (fields (field (name "PUBLISHER") "Altium Limited"))
      (libsource (lib "Miscellaneous Devices") (part "Res1"))
    )
    (comp (ref "R54")
      (value "BPR58-10mΩ")
      (footprint "R0.02")
      (description "采样电阻")
      (fields (field (name "PUBLISHER") "Altium Limited"))
      (libsource (lib "Miscellaneous Devices") (part "Res1"))
    )
    (comp (ref "R55")
      (value "510Ω")
      (footprint "0805R")
      (description "贴片电阻0805R")
      (fields (field (name "PUBLISHER") "Altium Limited"))
      (libsource (lib "Miscellaneous Devices") (part "Res3"))
    )
    (comp (ref "R56")
      (value "BPR58-10mΩ")
      (footprint "R0.02")
      (description "采样电阻")
      (fields (field (name "PUBLISHER") "Altium Limited"))
      (libsource (lib "Miscellaneous Devices") (part "Res1"))
    )
    (comp (ref "R57")
      (value "510Ω")
      (footprint "0805R")
      (description "贴片电阻0805R")
      (fields (field (name "PUBLISHER") "Altium Limited"))
      (libsource (lib "Miscellaneous Devices") (part "Res3"))
    )
    (comp (ref "R58")
      (value "100Ω")
      (footprint "0805R")
      (description "贴片电阻0805R")
      (fields (field (name "PUBLISHER") "Altium Limited"))
      (libsource (lib "Miscellaneous Devices") (part "Res2"))
    )
    (comp (ref "R59")
      (value "510Ω")
      (footprint "0805R")
      (description "贴片电阻0805R")
      (fields (field (name "PUBLISHER") "Altium Limited"))
      (libsource (lib "Miscellaneous Devices") (part "Res3"))
    )
    (comp (ref "R60")
      (value "510Ω")
      (footprint "0805R")
      (description "贴片电阻0805R")
      (fields (field (name "PUBLISHER") "Altium Limited"))
      (libsource (lib "Miscellaneous Devices") (part "Res3"))
    )
    (comp (ref "R61")
      (value "10mΩ")
      (footprint "R20mΩ")
      (description "康铜电阻")
      (fields (field (name "PUBLISHER") "Altium Limited"))
      (libsource (lib "Miscellaneous Devices") (part "Res1"))
    )
    (comp (ref "R62")
      (value "1.5kΩ")
      (footprint "1206R")
      (description "贴片电阻1206R")
      (fields (field (name "PUBLISHER") "Altium Limited"))
      (libsource (lib "Miscellaneous Devices") (part "Res3"))
    )
    (comp (ref "R63")
      (value "510Ω")
      (footprint "0805R")
      (description "贴片电阻0805R")
      (fields (field (name "PUBLISHER") "Altium Limited"))
      (libsource (lib "Miscellaneous Devices") (part "Res1"))
    )
    (comp (ref "R64")
      (value "5.1kΩ")
      (footprint "0805R")
      (description "贴片电阻0805R")
      (fields (field (name "PUBLISHER") "Altium Limited"))
      (libsource (lib "Miscellaneous Devices") (part "Res1"))
    )
    (comp (ref "R65")
      (value "510kΩ")
      (footprint "2010R")
      (description "贴片电阻2010R")
      (fields (field (name "PUBLISHER") "Altium Limited"))
      (libsource (lib "Miscellaneous Devices") (part "Res1"))
    )
    (comp (ref "R66")
      (value "1.2kΩ")
      (footprint "2010R")
      (description "贴片电阻2010R")
      (fields (field (name "PUBLISHER") "Altium Limited"))
      (libsource (lib "Miscellaneous Devices") (part "Res1"))
    )
    (comp (ref "R67")
      (value "1.2kΩ")
      (footprint "2010R")
      (description "贴片电阻2010R")
      (fields (field (name "PUBLISHER") "Altium Limited"))
      (libsource (lib "Miscellaneous Devices") (part "Res1"))
    )
    (comp (ref "R68")
      (value "1.2kΩ")
      (footprint "2010R")
      (description "贴片电阻")
      (fields (field (name "PUBLISHER") "Altium Limited"))
      (libsource (lib "Miscellaneous Devices") (part "Res1"))
    )
    (comp (ref "R69")
      (value "1.2kΩ")
      (footprint "2010R")
      (description "贴片电阻")
      (fields (field (name "PUBLISHER") "Altium Limited"))
      (libsource (lib "Miscellaneous Devices") (part "Res1"))
    )
    (comp (ref "T1")
      (value "EI33")
      (footprint "TRANFER")
      (description "EI33变压器")
      (libsource (lib "qudong") (part "Tranfer"))
    )
    (comp (ref "T2")
      (value "10mH")
      (footprint "CML")
      (description "共模电感")
      (fields (field (name "PUBLISHER") "Altium Limited"))
      (libsource (lib "Miscellaneous Devices") (part "Trans"))
    )
    (comp (ref "U1")
      (value "GBJ207")
      (footprint "BRIDGE208")
      (description "整流桥")
      (fields (field (name "ALTIUM_VALUE") "2A"))
      (libsource (lib "qudong") (part "Bridge_8A"))
    )
    (comp (ref "U2") (value "TOP256YN") (footprint "TOP256YN") (libsource (lib "qudong") (part "TOP256YN")))
    (comp (ref "U3") (value "PC817") (footprint "PC817") (libsource (lib "qudong") (part "PC817")))
    (comp (ref "U4") (value "TL431") (footprint "SO8") (libsource (lib "qudong") (part "TL431_SO8")))
    (comp (ref "U5")
      (value "GBU2506")
      (footprint "Bridge_8A")
      (description "整流桥")
      (libsource (lib "qudong") (part "Bridge_8A"))
    )
    (comp (ref "U6")
      (value "GBU2506")
      (footprint "Bridge_8A")
      (description "整流桥")
      (libsource (lib "qudong") (part "Bridge_8A"))
    )
    (comp (ref "U7") (value "TL431") (footprint "SO8") (libsource (lib "qudong") (part "TL431_SO8")))
    (comp (ref "U8")
      (value "LM339M")
      (footprint "SO14")
      (fields
        (field (name "MANUFACTURER") "National Semiconductor")
        (field (name "DIGIKEYPARTNUMBER") "LM339MXCT-ND")
        (field (name "PUBLISHER") "Altium Limited")
      )
      (libsource (lib "NSC Amplifier") (part "LM339M"))
    )
    (comp (ref "U9") (value "TLP701") (footprint "ACPI-P480") (libsource (lib "qudong") (part "TLP701")))
    (comp (ref "U10")
      (value "FSBB30CH60")
      (footprint "FSBS10CH60")
      (description "IPM_FSBB30CH60")
      (libsource (lib "qudong") (part "IPM_FSBS10CH60"))
    )
    (comp (ref "U11") (value "HCPL-7840") (footprint "HCPL7840") (libsource (lib "pcb") (part "HCPL-7840")))
    (comp (ref "U12") (value "ULN2003") (footprint "SO16") (libsource (lib "qudong") (part "ULN2003")))
    (comp (ref "U13")
      (value "ACPL-P480")
      (footprint "ACPI-P480")
      (libsource (lib "qudong") (part "ACPI-P480"))
    )
    (comp (ref "U14") (value "HCPL-7840") (footprint "HCPL7840") (libsource (lib "pcb") (part "HCPL-7840")))
    (comp (ref "U15")
      (value "ACPL-P480")
      (footprint "ACPI-P480")
      (libsource (lib "qudong") (part "ACPI-P480"))
    )
    (comp (ref "U16") (value "TLP281-1") (footprint "TLP281") (libsource (lib "mysch") (part "TLP181/PC357")))
    (comp (ref "U17") (value "TLP281-1") (footprint "TLP281") (libsource (lib "mysch") (part "TLP181/PC357")))
    (comp (ref "U18") (value "TLP281-1") (footprint "TLP281") (libsource (lib "mysch") (part "TLP181/PC357")))
    (comp (ref "U19")
      (value "ACPL-P480")
      (footprint "ACPI-P480")
      (libsource (lib "qudong") (part "ACPI-P480"))
    )
    (comp (ref "U20") (value "TLP281-1") (footprint "TLP281") (libsource (lib "mysch") (part "TLP181/PC357")))
    (comp (ref "U21")
      (value "ACPL-P480")
      (footprint "ACPI-P480")
      (libsource (lib "qudong") (part "ACPI-P480"))
    )
    (comp (ref "U22")
      (value "ACPL-P480")
      (footprint "ACPI-P480")
      (libsource (lib "qudong") (part "ACPI-P480"))
    )
    (comp (ref "U23")
      (value "TLP281-1")
      (footprint "TLP281")
      (fields (field (name "PUBLISHER") "Altium Limited"))
      (libsource (lib "Miscellaneous Devices") (part "Optoisolator1"))
    )
    (comp (ref "U24")
      (value "ACPL-P480")
      (footprint "ACPI-P480")
      (libsource (lib "qudong") (part "ACPI-P480"))
    )
  )
  (nets
    (net (code "1") (name "/B") (class "Default")
      (node (ref "D16") (pin "1") (pinfunction "A_1") (pintype "passive"))
      (node (ref "P1") (pin "4") (pinfunction "4_4") (pintype "passive"))
      (node (ref "Q1") (pin "2") (pinfunction "C_2") (pintype "passive"))
      (node (ref "R21") (pin "1") (pinfunction "1_1") (pintype "passive"))
    )
    (net (code "2") (name "/GNDH") (class "Default")
      (node (ref "C20") (pin "2") (pinfunction "2_2") (pintype "passive"))
      (node (ref "C21") (pin "2") (pinfunction "2_2") (pintype "passive"))
      (node (ref "C24") (pin "1") (pinfunction "1_1") (pintype "passive"))
      (node (ref "C25") (pin "2") (pinfunction "2_2") (pintype "passive"))
      (node (ref "C26") (pin "1") (pinfunction "1_1") (pintype "passive"))
      (node (ref "C27") (pin "1") (pinfunction "1_1") (pintype "passive"))
      (node (ref "C28") (pin "1") (pinfunction "1_1") (pintype "passive"))
      (node (ref "C29") (pin "1") (pinfunction "1_1") (pintype "passive"))
      (node (ref "D14") (pin "2") (pinfunction "K_2") (pintype "passive"))
      (node (ref "L3") (pin "2") (pinfunction "2_2") (pintype "passive"))
      (node (ref "P2") (pin "14") (pinfunction "14_14") (pintype "passive"))
      (node (ref "P2") (pin "15") (pinfunction "15_15") (pintype "passive"))
      (node (ref "P2") (pin "16") (pinfunction "16_16") (pintype "passive"))
      (node (ref "P2") (pin "17") (pinfunction "17_17") (pintype "passive"))
      (node (ref "P2") (pin "18") (pinfunction "18_18") (pintype "passive"))
      (node (ref "P3") (pin "1") (pinfunction "1_1") (pintype "passive"))
      (node (ref "P3") (pin "11") (pinfunction "11_11") (pintype "passive"))
      (node (ref "P3") (pin "13") (pinfunction "13_13") (pintype "passive"))
      (node (ref "P3") (pin "15") (pinfunction "15_15") (pintype "passive"))
      (node (ref "P3") (pin "17") (pinfunction "17_17") (pintype "passive"))
      (node (ref "P3") (pin "19") (pinfunction "19_19") (pintype "passive"))
      (node (ref "P3") (pin "21") (pinfunction "21_21") (pintype "passive"))
      (node (ref "P3") (pin "3") (pinfunction "3_3") (pintype "passive"))
      (node (ref "P3") (pin "5") (pinfunction "5_5") (pintype "passive"))
      (node (ref "P3") (pin "7") (pinfunction "7_7") (pintype "passive"))
      (node (ref "P3") (pin "9") (pinfunction "9_9") (pintype "passive"))
      (node (ref "R12") (pin "2") (pinfunction "2_2") (pintype "passive"))
      (node (ref "T1") (pin "7") (pinfunction "V5VG_7") (pintype "passive"))
      (node (ref "U16") (pin "3") (pinfunction "3_3") (pintype "passive"))
      (node (ref "U17") (pin "3") (pinfunction "3_3") (pintype "passive"))
      (node (ref "U18") (pin "3") (pinfunction "3_3") (pintype "passive"))
      (node (ref "U20") (pin "3") (pinfunction "3_3") (pintype "passive"))
      (node (ref "U23") (pin "3") (pinfunction "E_3") (pintype "passive"))
      (node (ref "U4") (pin "2") (pinfunction "AN_2") (pintype "passive"))
      (node (ref "U4") (pin "3") (pinfunction "AN_3") (pintype "passive"))
      (node (ref "U4") (pin "6") (pinfunction "AN_6") (pintype "passive"))
      (node (ref "U4") (pin "7") (pinfunction "AN_7") (pintype "passive"))
    )
    (net (code "3") (name "/GNDHM") (class "Default")
      (node (ref "C22") (pin "2") (pinfunction "2_2") (pintype "passive"))
      (node (ref "C23") (pin "2") (pinfunction "2_2") (pintype "passive"))
      (node (ref "C48") (pin "1") (pinfunction "1_1") (pintype "passive"))
      (node (ref "C59") (pin "1") (pinfunction "1_1") (pintype "passive"))
      (node (ref "L3") (pin "1") (pinfunction "1_1") (pintype "passive"))
      (node (ref "P2") (pin "5") (pinfunction "5_5") (pintype "passive"))
      (node (ref "P2") (pin "6") (pinfunction "6_6") (pintype "passive"))
      (node (ref "U11") (pin "5") (pinfunction "46_5") (pintype "passive"))
      (node (ref "U14") (pin "5") (pinfunction "46_5") (pintype "passive"))
    )
    (net (code "4") (name "/GROUND") (class "Default")
      (node (ref "C27") (pin "2") (pinfunction "2_2") (pintype "passive"))
      (node (ref "C30") (pin "2") (pinfunction "2_2") (pintype "passive"))
      (node (ref "C31") (pin "2") (pinfunction "2_2") (pintype "passive"))
      (node (ref "C39") (pin "2") (pinfunction "2_2") (pintype "passive"))
      (node (ref "C43") (pin "2") (pinfunction "2_2") (pintype "passive"))
      (node (ref "P1") (pin "9") (pinfunction "9_9") (pintype "passive"))
    )
    (net (code "5") (name "/P+") (class "Default")
      (node (ref "C36") (pin "1") (pinfunction "1_1") (pintype "passive"))
      (node (ref "C37") (pin "1") (pinfunction "1_1") (pintype "passive"))
      (node (ref "C38") (pin "1") (pinfunction "1_1") (pintype "passive"))
      (node (ref "C62") (pin "2") (pinfunction "2_2") (pintype "passive"))
      (node (ref "D16") (pin "2") (pinfunction "K_2") (pintype "passive"))
      (node (ref "K1") (pin "1") (pinfunction "1_1") (pintype "passive"))
      (node (ref "P1") (pin "5") (pinfunction "5_5") (pintype "passive"))
      (node (ref "R17") (pin "1") (pinfunction "1_1") (pintype "passive"))
      (node (ref "R18") (pin "1") (pinfunction "1_1") (pintype "passive"))
      (node (ref "R21") (pin "2") (pinfunction "2_2") (pintype "passive"))
      (node (ref "R22") (pin "2") (pinfunction "2_2") (pintype "passive"))
      (node (ref "U10") (pin "27") (pinfunction "P_27") (pintype "passive"))
    )
    (net (code "6") (name "/P-") (class "Default")
      (node (ref "C36") (pin "2") (pinfunction "2_2") (pintype "passive"))
      (node (ref "C37") (pin "2") (pinfunction "2_2") (pintype "passive"))
      (node (ref "C38") (pin "2") (pinfunction "2_2") (pintype "passive"))
      (node (ref "C43") (pin "1") (pinfunction "1_1") (pintype "passive"))
      (node (ref "D15") (pin "2") (pinfunction "K_2") (pintype "passive"))
      (node (ref "L4") (pin "2") (pinfunction "2_2") (pintype "passive"))
      (node (ref "Q1") (pin "3") (pinfunction "E_3") (pintype "passive"))
      (node (ref "R19") (pin "2") (pinfunction "2_2") (pintype "passive"))
      (node (ref "R20") (pin "2") (pinfunction "2_2") (pintype "passive"))
      (node (ref "R61") (pin "2") (pinfunction "2_2") (pintype "passive"))
      (node (ref "U5") (pin "4") (pinfunction "DC-_4") (pintype "passive"))
      (node (ref "U6") (pin "4") (pinfunction "DC-_4") (pintype "passive"))
    )
    (net (code "7") (name "/ProtectBR") (class "Default")
      (node (ref "P3") (pin "14") (pinfunction "14_14") (pintype "passive"))
      (node (ref "U18") (pin "4") (pinfunction "4_4") (pintype "passive"))
    )
    (net (code "8") (name "/ProtectIPM") (class "Default")
      (node (ref "P3") (pin "22") (pinfunction "22_22") (pintype "passive"))
      (node (ref "U23") (pin "4") (pinfunction "C_4") (pintype "passive"))
    )
    (net (code "9") (name "/ProtectLV") (class "Default")
      (node (ref "P3") (pin "18") (pinfunction "18_18") (pintype "passive"))
      (node (ref "U17") (pin "4") (pinfunction "4_4") (pintype "passive"))
    )
    (net (code "10") (name "/ProtectOV") (class "Default")
      (node (ref "P3") (pin "16") (pinfunction "16_16") (pintype "passive"))
      (node (ref "U20") (pin "4") (pinfunction "4_4") (pintype "passive"))
    )
    (net (code "11") (name "/ProtectST") (class "Default")
      (node (ref "P3") (pin "20") (pinfunction "20_20") (pintype "passive"))
      (node (ref "U16") (pin "4") (pinfunction "4_4") (pintype "passive"))
    )
    (net (code "12") (name "/U") (class "Default")
      (node (ref "P1") (pin "6") (pinfunction "6_6") (pintype "passive"))
      (node (ref "R51") (pin "2") (pinfunction "2_2") (pintype "passive"))
      (node (ref "U10") (pin "24") (pinfunction "U_24") (pintype "passive"))
    )
    (net (code "13") (name "/UH") (class "Default")
      (node (ref "U10") (pin "9") (pinfunction "IN(UH)_9") (pintype "passive"))
      (node (ref "U22") (pin "5") (pinfunction "VO_5") (pintype "passive"))
    )
    (net (code "14") (name "/UL") (class "Default")
      (node (ref "U10") (pin "3") (pinfunction "IN(UL)_3") (pintype "passive"))
      (node (ref "U24") (pin "5") (pinfunction "VO_5") (pintype "passive"))
    )
    (net (code "15") (name "/V") (class "Default")
      (node (ref "P1") (pin "7") (pinfunction "7_7") (pintype "passive"))
      (node (ref "R56") (pin "2") (pinfunction "2_2") (pintype "passive"))
      (node (ref "R58") (pin "1") (pinfunction "1_1") (pintype "passive"))
    )
    (net (code "16") (name "/V+") (class "Default")
      (node (ref "P2") (pin "2") (pinfunction "2_2") (pintype "passive"))
      (node (ref "U14") (pin "7") (pinfunction "44_7") (pintype "passive"))
    )
    (net (code "17") (name "/V-") (class "Default")
      (node (ref "P2") (pin "1") (pinfunction "1_1") (pintype "passive"))
      (node (ref "U14") (pin "6") (pinfunction "45_6") (pintype "passive"))
    )
    (net (code "18") (name "/V1") (class "Default")
      (node (ref "C61") (pin "2") (pinfunction "2_2") (pintype "passive"))
      (node (ref "C63") (pin "2") (pinfunction "2_2") (pintype "passive"))
      (node (ref "D18") (pin "1") (pinfunction "A_1") (pintype "passive"))
      (node (ref "R45") (pin "2") (pinfunction "2_2") (pintype "passive"))
      (node (ref "R56") (pin "1") (pinfunction "1_1") (pintype "passive"))
      (node (ref "U10") (pin "25") (pinfunction "V_25") (pintype "passive"))
      (node (ref "U14") (pin "3") (pinfunction "41_3") (pintype "passive"))
      (node (ref "U14") (pin "4") (pinfunction "42_4") (pintype "passive"))
    )
    (net (code "19") (name "/V1G") (class "Default")
      (node (ref "C1") (pin "1") (pinfunction "1_1") (pintype "passive"))
      (node (ref "C2") (pin "2") (pinfunction "2_2") (pintype "passive"))
      (node (ref "C60") (pin "1") (pinfunction "1_1") (pintype "passive"))
      (node (ref "D2") (pin "1") (pinfunction "A_1") (pintype "passive"))
      (node (ref "R51") (pin "1") (pinfunction "1_1") (pintype "passive"))
      (node (ref "R66") (pin "1") (pinfunction "1_1") (pintype "passive"))
      (node (ref "R67") (pin "1") (pinfunction "1_1") (pintype "passive"))
      (node (ref "T1") (pin "17") (pinfunction "V3G_17") (pintype "passive"))
      (node (ref "U10") (pin "12") (pinfunction "Vs(U)_12") (pintype "passive"))
    )
    (net (code "20") (name "/V1V") (class "Default")
      (node (ref "C1") (pin "2") (pinfunction "2_2") (pintype "passive"))
      (node (ref "C2") (pin "1") (pinfunction "1_1") (pintype "passive"))
      (node (ref "C60") (pin "2") (pinfunction "2_2") (pintype "passive"))
      (node (ref "D1") (pin "2") (pinfunction "K_2") (pintype "passive"))
      (node (ref "D2") (pin "2") (pinfunction "K_2") (pintype "passive"))
      (node (ref "R66") (pin "2") (pinfunction "2_2") (pintype "passive"))
      (node (ref "R67") (pin "2") (pinfunction "2_2") (pintype "passive"))
      (node (ref "U10") (pin "11") (pinfunction "Vb(U)_11") (pintype "passive"))
    )
    (net (code "21") (name "/V2G") (class "Default")
      (node (ref "C3") (pin "1") (pinfunction "1_1") (pintype "passive"))
      (node (ref "C4") (pin "2") (pinfunction "2_2") (pintype "passive"))
      (node (ref "C58") (pin "2") (pinfunction "2_2") (pintype "passive"))
      (node (ref "D4") (pin "1") (pinfunction "A_1") (pintype "passive"))
      (node (ref "R45") (pin "1") (pinfunction "1_1") (pintype "passive"))
      (node (ref "R68") (pin "1") (pinfunction "1_1") (pintype "passive"))
      (node (ref "T1") (pin "15") (pinfunction "V2G_15") (pintype "passive"))
      (node (ref "U10") (pin "16") (pinfunction "Vs(V)_16") (pintype "passive"))
    )
    (net (code "22") (name "/V2V") (class "Default")
      (node (ref "C3") (pin "2") (pinfunction "2_2") (pintype "passive"))
      (node (ref "C4") (pin "1") (pinfunction "1_1") (pintype "passive"))
      (node (ref "C58") (pin "1") (pinfunction "1_1") (pintype "passive"))
      (node (ref "D3") (pin "2") (pinfunction "K_2") (pintype "passive"))
      (node (ref "D4") (pin "2") (pinfunction "K_2") (pintype "passive"))
      (node (ref "R42") (pin "2") (pinfunction "2_2") (pintype "passive"))
      (node (ref "R68") (pin "2") (pinfunction "2_2") (pintype "passive"))
      (node (ref "U10") (pin "15") (pinfunction "Vb(V)_15") (pintype "passive"))
    )
    (net (code "23") (name "/V3G") (class "Default")
      (node (ref "C49") (pin "1") (pinfunction "1_1") (pintype "passive"))
      (node (ref "C5") (pin "1") (pinfunction "1_1") (pintype "passive"))
      (node (ref "C6") (pin "2") (pinfunction "2_2") (pintype "passive"))
      (node (ref "D6") (pin "1") (pinfunction "A_1") (pintype "passive"))
      (node (ref "R40") (pin "1") (pinfunction "1_1") (pintype "passive"))
      (node (ref "R69") (pin "1") (pinfunction "1_1") (pintype "passive"))
      (node (ref "T1") (pin "13") (pinfunction "V1G_13") (pintype "passive"))
      (node (ref "U10") (pin "20") (pinfunction "Vs(W)_20") (pintype "passive"))
    )
    (net (code "24") (name "/V3V") (class "Default")
      (node (ref "C49") (pin "2") (pinfunction "2_2") (pintype "passive"))
      (node (ref "C5") (pin "2") (pinfunction "2_2") (pintype "passive"))
      (node (ref "C6") (pin "1") (pinfunction "1_1") (pintype "passive"))
      (node (ref "D5") (pin "2") (pinfunction "K_2") (pintype "passive"))
      (node (ref "D6") (pin "2") (pinfunction "K_2") (pintype "passive"))
      (node (ref "R43") (pin "2") (pinfunction "2_2") (pintype "passive"))
      (node (ref "R69") (pin "2") (pinfunction "2_2") (pintype "passive"))
      (node (ref "U10") (pin "19") (pinfunction "Vb(W)_19") (pintype "passive"))
    )
    (net (code "25") (name "/VCC-10V") (class "Default")
      (node (ref "C17") (pin "1") (pinfunction "1_1") (pintype "passive"))
      (node (ref "C18") (pin "2") (pinfunction "2_2") (pintype "passive"))
      (node (ref "D10") (pin "1") (pinfunction "A_1") (pintype "passive"))
      (node (ref "D11") (pin "1") (pinfunction "A_1") (pintype "passive"))
      (node (ref "U9") (pin "4") (pinfunction "GND_4") (pintype "passive"))
    )
    (net (code "26") (name "/VCC5V") (class "Default")
      (node (ref "C13") (pin "2") (pinfunction "2_2") (pintype "passive"))
      (node (ref "C15") (pin "1") (pinfunction "1_1") (pintype "passive"))
      (node (ref "C16") (pin "1") (pinfunction "1_1") (pintype "passive"))
      (node (ref "C47") (pin "2") (pinfunction "2_2") (pintype "passive"))
      (node (ref "C52") (pin "2") (pinfunction "2_2") (pintype "passive"))
      (node (ref "C53") (pin "2") (pinfunction "2_2") (pintype "passive"))
      (node (ref "C54") (pin "2") (pinfunction "2_2") (pintype "passive"))
      (node (ref "C55") (pin "2") (pinfunction "2_2") (pintype "passive"))
      (node (ref "C56") (pin "2") (pinfunction "2_2") (pintype "passive"))
      (node (ref "C57") (pin "2") (pinfunction "2_2") (pintype "passive"))
      (node (ref "LM1") (pin "3") (pinfunction "Vout_3") (pintype "passive"))
      (node (ref "R41") (pin "1") (pinfunction "1_1") (pintype "passive"))
      (node (ref "R44") (pin "1") (pinfunction "1_1") (pintype "passive"))
      (node (ref "R46") (pin "1") (pinfunction "1_1") (pintype "passive"))
      (node (ref "R47") (pin "1") (pinfunction "1_1") (pintype "passive"))
      (node (ref "R50") (pin "1") (pinfunction "1_1") (pintype "passive"))
      (node (ref "R53") (pin "2") (pinfunction "2_2") (pintype "passive"))
      (node (ref "R55") (pin "1") (pinfunction "1_1") (pintype "passive"))
      (node (ref "R57") (pin "1") (pinfunction "1_1") (pintype "passive"))
      (node (ref "R59") (pin "1") (pinfunction "1_1") (pintype "passive"))
      (node (ref "R60") (pin "1") (pinfunction "1_1") (pintype "passive"))
      (node (ref "R63") (pin "2") (pinfunction "2_2") (pintype "passive"))
      (node (ref "R64") (pin "2") (pinfunction "2_2") (pintype "passive"))
      (node (ref "U13") (pin "6") (pinfunction "VCC_6") (pintype "passive"))
      (node (ref "U15") (pin "6") (pinfunction "VCC_6") (pintype "passive"))
      (node (ref "U19") (pin "6") (pinfunction "VCC_6") (pintype "passive"))
      (node (ref "U21") (pin "6") (pinfunction "VCC_6") (pintype "passive"))
      (node (ref "U22") (pin "6") (pinfunction "VCC_6") (pintype "passive"))
      (node (ref "U24") (pin "6") (pinfunction "VCC_6") (pintype "passive"))
      (node (ref "U8") (pin "3") (pinfunction "V+_3") (pintype "power_in"))
    )
    (net (code "27") (name "/VCC5VH") (class "Default")
      (node (ref "C20") (pin "1") (pinfunction "1_1") (pintype "passive"))
      (node (ref "C21") (pin "1") (pinfunction "1_1") (pintype "passive"))
      (node (ref "C24") (pin "2") (pinfunction "2_2") (pintype "passive"))
      (node (ref "L1") (pin "2") (pinfunction "2_2") (pintype "passive"))
      (node (ref "L2") (pin "2") (pinfunction "2_2") (pintype "passive"))
      (node (ref "P2") (pin "10") (pinfunction "10_10") (pintype "passive"))
      (node (ref "P2") (pin "11") (pinfunction "11_11") (pintype "passive"))
      (node (ref "P2") (pin "12") (pinfunction "12_12") (pintype "passive"))
      (node (ref "P2") (pin "13") (pinfunction "13_13") (pintype "passive"))
      (node (ref "P2") (pin "9") (pinfunction "9_9") (pintype "passive"))
      (node (ref "R11") (pin "2") (pinfunction "2_2") (pintype "passive"))
      (node (ref "R9") (pin "2") (pinfunction "2_2") (pintype "passive"))
    )
    (net (code "28") (name "/VCC5VHM") (class "Default")
      (node (ref "C22") (pin "1") (pinfunction "1_1") (pintype "passive"))
      (node (ref "C23") (pin "1") (pinfunction "1_1") (pintype "passive"))
      (node (ref "C48") (pin "2") (pinfunction "2_2") (pintype "passive"))
      (node (ref "C59") (pin "2") (pinfunction "2_2") (pintype "passive"))
      (node (ref "L2") (pin "1") (pinfunction "1_1") (pintype "passive"))
      (node (ref "P2") (pin "7") (pinfunction "7_7") (pintype "passive"))
      (node (ref "P2") (pin "8") (pinfunction "8_8") (pintype "passive"))
      (node (ref "U11") (pin "8") (pinfunction "43_8") (pintype "passive"))
      (node (ref "U14") (pin "8") (pinfunction "43_8") (pintype "passive"))
    )
    (net (code "29") (name "/VCC15V") (class "Default")
      (node (ref "C14") (pin "1") (pinfunction "1_1") (pintype "passive"))
      (node (ref "C66") (pin "1") (pinfunction "1_1") (pintype "passive"))
      (node (ref "C67") (pin "2") (pinfunction "2_2") (pintype "passive"))
      (node (ref "C68") (pin "2") (pinfunction "2_2") (pintype "passive"))
      (node (ref "C9") (pin "2") (pinfunction "2_2") (pintype "passive"))
      (node (ref "D7") (pin "2") (pinfunction "K_2") (pintype "passive"))
      (node (ref "D8") (pin "2") (pinfunction "K_2") (pintype "passive"))
      (node (ref "LM1") (pin "1") (pinfunction "Vin_1") (pintype "passive"))
      (node (ref "R34") (pin "2") (pinfunction "2_2") (pintype "passive"))
      (node (ref "R35") (pin "2") (pinfunction "2_2") (pintype "passive"))
      (node (ref "U10") (pin "1") (pinfunction "Vcc(L)_1") (pintype "passive"))
      (node (ref "U10") (pin "10") (pinfunction "Vcc(UH)_10") (pintype "passive"))
      (node (ref "U10") (pin "14") (pinfunction "Vcc(VH)_14") (pintype "passive"))
      (node (ref "U10") (pin "18") (pinfunction "Vcc(WH)_18") (pintype "passive"))
      (node (ref "U9") (pin "6") (pinfunction "VCC_6") (pintype "passive"))
    )
    (net (code "30") (name "/VH") (class "Default")
      (node (ref "U10") (pin "13") (pinfunction "IN(VH)_13") (pintype "passive"))
      (node (ref "U19") (pin "5") (pinfunction "VO_5") (pintype "passive"))
    )
    (net (code "31") (name "/VL") (class "Default")
      (node (ref "U10") (pin "4") (pinfunction "IN(VL)_4") (pintype "passive"))
      (node (ref "U21") (pin "5") (pinfunction "VO_5") (pintype "passive"))
    )
    (net (code "32") (name "/W") (class "Default")
      (node (ref "P1") (pin "8") (pinfunction "8_8") (pintype "passive"))
      (node (ref "R52") (pin "1") (pinfunction "1_1") (pintype "passive"))
      (node (ref "R54") (pin "2") (pinfunction "2_2") (pintype "passive"))
    )
    (net (code "33") (name "/W+") (class "Default")
      (node (ref "P2") (pin "4") (pinfunction "4_4") (pintype "passive"))
      (node (ref "U11") (pin "7") (pinfunction "44_7") (pintype "passive"))
    )
    (net (code "34") (name "/W-") (class "Default")
      (node (ref "P2") (pin "3") (pinfunction "3_3") (pintype "passive"))
      (node (ref "U11") (pin "6") (pinfunction "45_6") (pintype "passive"))
    )
    (net (code "35") (name "/W1") (class "Default")
      (node (ref "C50") (pin "2") (pinfunction "2_2") (pintype "passive"))
      (node (ref "C51") (pin "2") (pinfunction "2_2") (pintype "passive"))
      (node (ref "D17") (pin "1") (pinfunction "A_1") (pintype "passive"))
      (node (ref "R40") (pin "2") (pinfunction "2_2") (pintype "passive"))
      (node (ref "R54") (pin "1") (pinfunction "1_1") (pintype "passive"))
      (node (ref "U10") (pin "26") (pinfunction "W_26") (pintype "passive"))
      (node (ref "U11") (pin "3") (pinfunction "41_3") (pintype "passive"))
      (node (ref "U11") (pin "4") (pinfunction "42_4") (pintype "passive"))
    )
    (net (code "36") (name "/WH") (class "Default")
      (node (ref "U10") (pin "17") (pinfunction "IN(WH)_17") (pintype "passive"))
      (node (ref "U13") (pin "5") (pinfunction "VO_5") (pintype "passive"))
    )
    (net (code "37") (name "/WL") (class "Default")
      (node (ref "U10") (pin "5") (pinfunction "IN(WL)_5") (pintype "passive"))
      (node (ref "U15") (pin "5") (pinfunction "VO_5") (pintype "passive"))
    )
    (net (code "38") (name "GND") (class "Default")
      (node (ref "C13") (pin "1") (pinfunction "1_1") (pintype "passive"))
      (node (ref "C14") (pin "2") (pinfunction "2_2") (pintype "passive"))
      (node (ref "C15") (pin "2") (pinfunction "2_2") (pintype "passive"))
      (node (ref "C16") (pin "2") (pinfunction "2_2") (pintype "passive"))
      (node (ref "C17") (pin "2") (pinfunction "2_2") (pintype "passive"))
      (node (ref "C18") (pin "1") (pinfunction "1_1") (pintype "passive"))
      (node (ref "C44") (pin "1") (pinfunction "1_1") (pintype "passive"))
      (node (ref "C45") (pin "2") (pinfunction "2_2") (pintype "passive"))
      (node (ref "C46") (pin "2") (pinfunction "2_2") (pintype "passive"))
      (node (ref "C47") (pin "1") (pinfunction "1_1") (pintype "passive"))
      (node (ref "C52") (pin "1") (pinfunction "1_1") (pintype "passive"))
      (node (ref "C53") (pin "1") (pinfunction "1_1") (pintype "passive"))
      (node (ref "C54") (pin "1") (pinfunction "1_1") (pintype "passive"))
      (node (ref "C55") (pin "1") (pinfunction "1_1") (pintype "passive"))
      (node (ref "C56") (pin "1") (pinfunction "1_1") (pintype "passive"))
      (node (ref "C57") (pin "1") (pinfunction "1_1") (pintype "passive"))
      (node (ref "C64") (pin "2") (pinfunction "2_2") (pintype "passive"))
      (node (ref "C65") (pin "2") (pinfunction "2_2") (pintype "passive"))
      (node (ref "C66") (pin "2") (pinfunction "2_2") (pintype "passive"))
      (node (ref "C67") (pin "1") (pinfunction "1_1") (pintype "passive"))
      (node (ref "C68") (pin "1") (pinfunction "1_1") (pintype "passive"))
      (node (ref "C9") (pin "1") (pinfunction "1_1") (pintype "passive"))
      (node (ref "D11") (pin "2") (pinfunction "K_2") (pintype "passive"))
      (node (ref "D8") (pin "1") (pinfunction "A_1") (pintype "passive"))
      (node (ref "L4") (pin "1") (pinfunction "1_1") (pintype "passive"))
      (node (ref "LM1") (pin "2") (pinfunction "GND_2") (pintype "passive"))
      (node (ref "Q2") (pin "3") (pinfunction "C_3") (pintype "passive"))
      (node (ref "R26") (pin "1") (pinfunction "1_1") (pintype "passive"))
      (node (ref "T1") (pin "11") (pinfunction "V15VG_11") (pintype "passive"))
      (node (ref "U10") (pin "2") (pinfunction "COM_2") (pintype "passive"))
      (node (ref "U12") (pin "8") (pinfunction "GND_8") (pintype "passive"))
      (node (ref "U13") (pin "4") (pinfunction "GND_4") (pintype "passive"))
      (node (ref "U15") (pin "4") (pinfunction "GND_4") (pintype "passive"))
      (node (ref "U19") (pin "4") (pinfunction "GND_4") (pintype "passive"))
      (node (ref "U21") (pin "4") (pinfunction "GND_4") (pintype "passive"))
      (node (ref "U22") (pin "4") (pinfunction "GND_4") (pintype "passive"))
      (node (ref "U24") (pin "4") (pinfunction "GND_4") (pintype "passive"))
      (node (ref "U7") (pin "2") (pinfunction "AN_2") (pintype "passive"))
      (node (ref "U7") (pin "3") (pinfunction "AN_3") (pintype "passive"))
      (node (ref "U7") (pin "6") (pinfunction "AN_6") (pintype "passive"))
      (node (ref "U7") (pin "7") (pinfunction "AN_7") (pintype "passive"))
      (node (ref "U8") (pin "12") (pinfunction "GND_12") (pintype "power_in"))
    )
    (net (code "39") (name "Net-(C7-Pad1)") (class "Default")
      (node (ref "C7") (pin "1") (pinfunction "1_1") (pintype "passive"))
      (node (ref "R1") (pin "1") (pinfunction "1_1") (pintype "passive"))
      (node (ref "R2") (pin "1") (pinfunction "1_1") (pintype "passive"))
      (node (ref "R5") (pin "2") (pinfunction "2_2") (pintype "passive"))
    )
    (net (code "40") (name "Net-(C10-Pad1)") (class "Default")
      (node (ref "C10") (pin "1") (pinfunction "1_1") (pintype "passive"))
      (node (ref "F1") (pin "2") (pinfunction "2_2") (pintype "passive"))
      (node (ref "T2") (pin "1") (pinfunction "1_1") (pintype "passive"))
    )
    (net (code "41") (name "Net-(C10-Pad2)") (class "Default")
      (node (ref "C10") (pin "2") (pinfunction "2_2") (pintype "passive"))
      (node (ref "R4") (pin "2") (pinfunction "2_2") (pintype "passive"))
      (node (ref "T2") (pin "3") (pinfunction "3_3") (pintype "passive"))
    )
    (net (code "42") (name "Net-(C19-Pad2)") (class "Default")
      (node (ref "C19") (pin "2") (pinfunction "2_2") (pintype "passive"))
      (node (ref "R8") (pin "1") (pinfunction "1_1") (pintype "passive"))
    )
    (net (code "43") (name "Net-(C35-Pad1)") (class "Default")
      (node (ref "C35") (pin "1") (pinfunction "1_1") (pintype "passive"))
      (node (ref "R14") (pin "1") (pinfunction "1_1") (pintype "passive"))
    )
    (net (code "44") (name "Net-(C40-Pad1)") (class "Default")
      (node (ref "C40") (pin "1") (pinfunction "1_1") (pintype "passive"))
      (node (ref "F3") (pin "1") (pinfunction "1_1") (pintype "passive"))
      (node (ref "P1") (pin "2") (pinfunction "2_2") (pintype "passive"))
      (node (ref "R31") (pin "2") (pinfunction "2_2") (pintype "passive"))
    )
    (net (code "45") (name "Net-(C40-Pad2)") (class "Default")
      (node (ref "C40") (pin "2") (pinfunction "2_2") (pintype "passive"))
      (node (ref "F2") (pin "1") (pinfunction "1_1") (pintype "passive"))
      (node (ref "P1") (pin "3") (pinfunction "3_3") (pintype "passive"))
      (node (ref "R31") (pin "1") (pinfunction "1_1") (pintype "passive"))
    )
    (net (code "46") (name "Net-(C41-Pad1)") (class "Default")
      (node (ref "C41") (pin "1") (pinfunction "1_1") (pintype "passive"))
      (node (ref "C42") (pin "1") (pinfunction "1_1") (pintype "passive"))
      (node (ref "P1") (pin "1") (pinfunction "1_1") (pintype "passive"))
      (node (ref "R32") (pin "2") (pinfunction "2_2") (pintype "passive"))
      (node (ref "R33") (pin "2") (pinfunction "2_2") (pintype "passive"))
      (node (ref "U6") (pin "2") (pinfunction "AC_2") (pintype "passive"))
      (node (ref "U6") (pin "3") (pinfunction "AC_3") (pintype "passive"))
    )
    (net (code "47") (name "Net-(C41-Pad2)") (class "Default")
      (node (ref "C41") (pin "2") (pinfunction "2_2") (pintype "passive"))
      (node (ref "F2") (pin "2") (pinfunction "2_2") (pintype "passive"))
      (node (ref "R32") (pin "1") (pinfunction "1_1") (pintype "passive"))
      (node (ref "U5") (pin "2") (pinfunction "AC_2") (pintype "passive"))
    )
    (net (code "48") (name "Net-(C42-Pad2)") (class "Default")
      (node (ref "C42") (pin "2") (pinfunction "2_2") (pintype "passive"))
      (node (ref "F3") (pin "2") (pinfunction "2_2") (pintype "passive"))
      (node (ref "R33") (pin "1") (pinfunction "1_1") (pintype "passive"))
      (node (ref "U5") (pin "3") (pinfunction "AC_3") (pintype "passive"))
    )
    (net (code "49") (name "Net-(D1-A)") (class "Default")
      (node (ref "D1") (pin "1") (pinfunction "A_1") (pintype "passive"))
      (node (ref "T1") (pin "18") (pinfunction "V3V_18") (pintype "passive"))
    )
    (net (code "50") (name "Net-(D3-A)") (class "Default")
      (node (ref "D3") (pin "1") (pinfunction "A_1") (pintype "passive"))
      (node (ref "T1") (pin "16") (pinfunction "V2V_16") (pintype "passive"))
    )
    (net (code "51") (name "Net-(D5-A)") (class "Default")
      (node (ref "D5") (pin "1") (pinfunction "A_1") (pintype "passive"))
      (node (ref "T1") (pin "14") (pinfunction "V1V_14") (pintype "passive"))
    )
    (net (code "52") (name "Net-(D7-A)") (class "Default")
      (node (ref "D7") (pin "1") (pinfunction "A_1") (pintype "passive"))
      (node (ref "T1") (pin "12") (pinfunction "V15VV_12") (pintype "passive"))
    )
    (net (code "53") (name "Net-(D9-A)") (class "Default")
      (node (ref "D9") (pin "1") (pinfunction "A_1") (pintype "passive"))
      (node (ref "T1") (pin "3") (pinfunction "VSin_3") (pintype "passive"))
      (node (ref "U2") (pin "7") (pinfunction "D_7") (pintype "passive"))
    )
    (net (code "54") (name "Net-(D9-K)") (class "Default")
      (node (ref "D9") (pin "2") (pinfunction "K_2") (pintype "passive"))
      (node (ref "R5") (pin "1") (pinfunction "1_1") (pintype "passive"))
    )
    (net (code "55") (name "Net-(D10-K)") (class "Default")
      (node (ref "D10") (pin "2") (pinfunction "K_2") (pintype "passive"))
      (node (ref "T1") (pin "10") (pinfunction "V-10VV_10") (pintype "passive"))
    )
    (net (code "56") (name "Net-(D12-A)") (class "Default")
      (node (ref "D12") (pin "1") (pinfunction "A_1") (pintype "passive"))
      (node (ref "T1") (pin "5") (pinfunction "VBV_5") (pintype "passive"))
    )
    (net (code "57") (name "Net-(D12-K)") (class "Default")
      (node (ref "C34") (pin "1") (pinfunction "1_1") (pintype "passive"))
      (node (ref "D12") (pin "2") (pinfunction "K_2") (pintype "passive"))
      (node (ref "U3") (pin "4") (pinfunction "Oin_4") (pintype "passive"))
    )
    (net (code "58") (name "Net-(D13-A)") (class "Default")
      (node (ref "D13") (pin "1") (pinfunction "A_1") (pintype "passive"))
      (node (ref "R8") (pin "2") (pinfunction "2_2") (pintype "passive"))
      (node (ref "T1") (pin "8") (pinfunction "V5VV_8") (pintype "passive"))
    )
    (net (code "59") (name "Net-(D13-K)") (class "Default")
      (node (ref "C19") (pin "1") (pinfunction "1_1") (pintype "passive"))
      (node (ref "C25") (pin "1") (pinfunction "1_1") (pintype "passive"))
      (node (ref "C26") (pin "2") (pinfunction "2_2") (pintype "passive"))
      (node (ref "D13") (pin "2") (pinfunction "K_2") (pintype "passive"))
      (node (ref "L1") (pin "1") (pinfunction "1_1") (pintype "passive"))
      (node (ref "R10") (pin "1") (pinfunction "1_1") (pintype "passive"))
    )
    (net (code "60") (name "Net-(D14-A)") (class "Default")
      (node (ref "D14") (pin "1") (pinfunction "A_1") (pintype "passive"))
      (node (ref "R11") (pin "1") (pinfunction "1_1") (pintype "passive"))
    )
    (net (code "61") (name "Net-(D15-A)") (class "Default")
      (node (ref "D15") (pin "1") (pinfunction "A_1") (pintype "passive"))
      (node (ref "R65") (pin "2") (pinfunction "2_2") (pintype "passive"))
    )
    (net (code "62") (name "Net-(D17-K)") (class "Default")
      (node (ref "C50") (pin "1") (pinfunction "1_1") (pintype "passive"))
      (node (ref "D17") (pin "2") (pinfunction "K_2") (pintype "passive"))
      (node (ref "R49") (pin "1") (pinfunction "1_1") (pintype "passive"))
      (node (ref "U11") (pin "1") (pintype "passive"))
    )
    (net (code "63") (name "Net-(D18-K)") (class "Default")
      (node (ref "C61") (pin "1") (pinfunction "1_1") (pintype "passive"))
      (node (ref "D18") (pin "2") (pinfunction "K_2") (pintype "passive"))
      (node (ref "R48") (pin "1") (pinfunction "1_1") (pintype "passive"))
      (node (ref "U14") (pin "1") (pintype "passive"))
    )
    (net (code "64") (name "Net-(F1-Pad1)") (class "Default")
      (node (ref "F1") (pin "1") (pinfunction "1_1") (pintype "passive"))
      (node (ref "P1") (pin "11") (pinfunction "11_11") (pintype "passive"))
      (node (ref "R6") (pin "1") (pinfunction "1_1") (pintype "passive"))
    )
    (net (code "65") (name "Net-(K1-Pad2)") (class "Default")
      (node (ref "K1") (pin "2") (pinfunction "2_2") (pintype "passive"))
      (node (ref "R19") (pin "1") (pinfunction "1_1") (pintype "passive"))
      (node (ref "R20") (pin "1") (pinfunction "1_1") (pintype "passive"))
    )
    (net (code "66") (name "Net-(K1-Pad4)") (class "Default")
      (node (ref "K1") (pin "4") (pinfunction "4_4") (pintype "passive"))
      (node (ref "R34") (pin "1") (pinfunction "1_1") (pintype "passive"))
      (node (ref "R35") (pin "1") (pinfunction "1_1") (pintype "passive"))
    )
    (net (code "67") (name "Net-(P1-Pad10)") (class "Default")
      (node (ref "P1") (pin "10") (pinfunction "10_10") (pintype "passive"))
      (node (ref "R4") (pin "1") (pinfunction "1_1") (pintype "passive"))
      (node (ref "R6") (pin "2") (pinfunction "2_2") (pintype "passive"))
    )
    (net (code "68") (name "Net-(Q1-G)") (class "Default")
      (node (ref "Q1") (pin "1") (pinfunction "G_1") (pintype "passive"))
      (node (ref "U9") (pin "5") (pinfunction "VO_5") (pintype "passive"))
    )
    (net (code "69") (name "Net-(Q2-B)") (class "Default")
      (node (ref "Q2") (pin "1") (pinfunction "B_1") (pintype "passive"))
      (node (ref "R64") (pin "1") (pinfunction "1_1") (pintype "passive"))
      (node (ref "U10") (pin "6") (pinfunction "Vfo_6") (pintype "passive"))
    )
    (net (code "70") (name "Net-(Q2-E)") (class "Default")
      (node (ref "Q2") (pin "2") (pinfunction "E_2") (pintype "passive"))
      (node (ref "U23") (pin "2") (pinfunction "K_2") (pintype "passive"))
    )
    (net (code "71") (name "Net-(R3-Pad1)") (class "Default")
      (node (ref "R3") (pin "1") (pinfunction "1_1") (pintype "passive"))
      (node (ref "R7") (pin "2") (pinfunction "2_2") (pintype "passive"))
    )
    (net (code "72") (name "Net-(R16-Pad1)") (class "Default")
      (node (ref "R16") (pin "1") (pinfunction "1_1") (pintype "passive"))
      (node (ref "R17") (pin "2") (pinfunction "2_2") (pintype "passive"))
    )
    (net (code "73") (name "Net-(R18-Pad2)") (class "Default")
      (node (ref "R18") (pin "2") (pinfunction "2_2") (pintype "passive"))
      (node (ref "R65") (pin "1") (pinfunction "1_1") (pintype "passive"))
    )
    (net (code "74") (name "Net-(R42-Pad1)") (class "Default")
      (node (ref "R42") (pin "1") (pinfunction "1_1") (pintype "passive"))
      (node (ref "R48") (pin "2") (pinfunction "2_2") (pintype "passive"))
    )
    (net (code "75") (name "Net-(R43-Pad1)") (class "Default")
      (node (ref "R43") (pin "1") (pinfunction "1_1") (pintype "passive"))
      (node (ref "R49") (pin "2") (pinfunction "2_2") (pintype "passive"))
    )
    (net (code "76") (name "Net-(R55-Pad2)") (class "Default")
      (node (ref "R55") (pin "2") (pinfunction "2_2") (pintype "passive"))
      (node (ref "U16") (pin "1") (pinfunction "1_1") (pintype "passive"))
    )
    (net (code "77") (name "Net-(R57-Pad2)") (class "Default")
      (node (ref "R57") (pin "2") (pinfunction "2_2") (pintype "passive"))
      (node (ref "U17") (pin "1") (pinfunction "1_1") (pintype "passive"))
    )
    (net (code "78") (name "Net-(R59-Pad2)") (class "Default")
      (node (ref "R59") (pin "2") (pinfunction "2_2") (pintype "passive"))
      (node (ref "U18") (pin "1") (pinfunction "1_1") (pintype "passive"))
    )
    (net (code "79") (name "Net-(R60-Pad2)") (class "Default")
      (node (ref "R60") (pin "2") (pinfunction "2_2") (pintype "passive"))
      (node (ref "U20") (pin "1") (pinfunction "1_1") (pintype "passive"))
    )
    (net (code "80") (name "Net-(T1-VBG)") (class "Default")
      (node (ref "C29") (pin "2") (pinfunction "2_2") (pintype "passive"))
      (node (ref "C31") (pin "1") (pinfunction "1_1") (pintype "passive"))
      (node (ref "C33") (pin "1") (pinfunction "1_1") (pintype "passive"))
      (node (ref "C34") (pin "2") (pinfunction "2_2") (pintype "passive"))
      (node (ref "C35") (pin "2") (pinfunction "2_2") (pintype "passive"))
      (node (ref "C8") (pin "2") (pinfunction "2_2") (pintype "passive"))
      (node (ref "R15") (pin "1") (pinfunction "1_1") (pintype "passive"))
      (node (ref "T1") (pin "4") (pinfunction "VBG_4") (pintype "passive"))
      (node (ref "U1") (pin "4") (pinfunction "DC-_4") (pintype "passive"))
      (node (ref "U2") (pin "4") (pinfunction "S_4") (pintype "passive"))
      (node (ref "U2") (pin "5") (pinfunction "F_5") (pintype "passive"))
    )
    (net (code "81") (name "Net-(T2-Pad2)") (class "Default")
      (node (ref "T2") (pin "2") (pinfunction "2_2") (pintype "passive"))
      (node (ref "U1") (pin "3") (pinfunction "AC_3") (pintype "passive"))
    )
    (net (code "82") (name "Net-(T2-Pad4)") (class "Default")
      (node (ref "T2") (pin "4") (pinfunction "4_4") (pintype "passive"))
      (node (ref "U1") (pin "2") (pinfunction "AC_2") (pintype "passive"))
    )
    (net (code "83") (name "Net-(U1-DC+)") (class "Default")
      (node (ref "C28") (pin "2") (pinfunction "2_2") (pintype "passive"))
      (node (ref "C30") (pin "1") (pinfunction "1_1") (pintype "passive"))
      (node (ref "C7") (pin "2") (pinfunction "2_2") (pintype "passive"))
      (node (ref "C8") (pin "1") (pinfunction "1_1") (pintype "passive"))
      (node (ref "R1") (pin "2") (pinfunction "2_2") (pintype "passive"))
      (node (ref "R2") (pin "2") (pinfunction "2_2") (pintype "passive"))
      (node (ref "R3") (pin "2") (pinfunction "2_2") (pintype "passive"))
      (node (ref "T1") (pin "1") (pinfunction "VSin_1") (pintype "passive"))
      (node (ref "U1") (pin "1") (pinfunction "DC+_1") (pintype "passive"))
    )
    (net (code "84") (name "Net-(U2-C)") (class "Default")
      (node (ref "C33") (pin "2") (pinfunction "2_2") (pintype "passive"))
      (node (ref "R14") (pin "2") (pinfunction "2_2") (pintype "passive"))
      (node (ref "U2") (pin "3") (pinfunction "C_3") (pintype "passive"))
      (node (ref "U3") (pin "3") (pinfunction "Oout_3") (pintype "passive"))
    )
    (net (code "85") (name "Net-(U2-V)") (class "Default")
      (node (ref "R7") (pin "1") (pinfunction "1_1") (pintype "passive"))
      (node (ref "U2") (pin "1") (pinfunction "V_1") (pintype "passive"))
    )
    (net (code "86") (name "Net-(U2-X)") (class "Default")
      (node (ref "R15") (pin "2") (pinfunction "2_2") (pintype "passive"))
      (node (ref "U2") (pin "2") (pinfunction "X_2") (pintype "passive"))
    )
    (net (code "87") (name "Net-(U3-Iin)") (class "Default")
      (node (ref "R10") (pin "2") (pinfunction "2_2") (pintype "passive"))
      (node (ref "R13") (pin "1") (pinfunction "1_1") (pintype "passive"))
      (node (ref "U3") (pin "1") (pinfunction "Iin_1") (pintype "passive"))
    )
    (net (code "88") (name "Net-(U3-Iout)") (class "Default")
      (node (ref "C32") (pin "2") (pinfunction "2_2") (pintype "passive"))
      (node (ref "R13") (pin "2") (pinfunction "2_2") (pintype "passive"))
      (node (ref "U3") (pin "2") (pinfunction "Iout_2") (pintype "passive"))
      (node (ref "U4") (pin "1") (pinfunction "CAT_1") (pintype "passive"))
    )
    (net (code "89") (name "Net-(U4-REF)") (class "Default")
      (node (ref "C32") (pin "1") (pinfunction "1_1") (pintype "passive"))
      (node (ref "R12") (pin "1") (pinfunction "1_1") (pintype "passive"))
      (node (ref "R9") (pin "1") (pinfunction "1_1") (pintype "passive"))
      (node (ref "U4") (pin "8") (pinfunction "REF_8") (pintype "passive"))
    )
    (net (code "90") (name "Net-(U5-DC+)") (class "Default")
      (node (ref "C39") (pin "1") (pinfunction "1_1") (pintype "passive"))
      (node (ref "K1") (pin "3") (pinfunction "3_3") (pintype "passive"))
      (node (ref "R16") (pin "2") (pinfunction "2_2") (pintype "passive"))
      (node (ref "U5") (pin "1") (pinfunction "DC+_1") (pintype "passive"))
      (node (ref "U6") (pin "1") (pinfunction "DC+_1") (pintype "passive"))
    )
    (net (code "91") (name "Net-(U7-CAT)") (class "Default")
      (node (ref "C44") (pin "2") (pinfunction "2_2") (pintype "passive"))
      (node (ref "C45") (pin "1") (pinfunction "1_1") (pintype "passive"))
      (node (ref "R47") (pin "2") (pinfunction "2_2") (pintype "passive"))
      (node (ref "U7") (pin "1") (pinfunction "CAT_1") (pintype "passive"))
      (node (ref "U7") (pin "8") (pinfunction "REF_8") (pintype "passive"))
      (node (ref "U8") (pin "10") (pinfunction "IN4-_10") (pintype "input"))
      (node (ref "U8") (pin "4") (pinfunction "IN1-_4") (pintype "input"))
      (node (ref "U8") (pin "7") (pinfunction "IN2+_7") (pintype "input"))
      (node (ref "U8") (pin "8") (pinfunction "IN3-_8") (pintype "input"))
    )
    (net (code "92") (name "Net-(U8A-IN1+)") (class "Default")
      (node (ref "C46") (pin "1") (pinfunction "1_1") (pintype "passive"))
      (node (ref "R22") (pin "1") (pinfunction "1_1") (pintype "passive"))
      (node (ref "R23") (pin "2") (pinfunction "2_2") (pintype "passive"))
      (node (ref "U8") (pin "5") (pinfunction "IN1+_5") (pintype "input"))
    )
    (net (code "93") (name "Net-(U8B-IN2-)") (class "Default")
      (node (ref "R23") (pin "1") (pinfunction "1_1") (pintype "passive"))
      (node (ref "R24") (pin "2") (pinfunction "2_2") (pintype "passive"))
      (node (ref "U8") (pin "6") (pinfunction "IN2-_6") (pintype "input"))
    )
    (net (code "94") (name "Net-(U8C-IN3+)") (class "Default")
      (node (ref "R24") (pin "1") (pinfunction "1_1") (pintype "passive"))
      (node (ref "R25") (pin "2") (pinfunction "2_2") (pintype "passive"))
      (node (ref "U8") (pin "9") (pinfunction "IN3+_9") (pintype "input"))
    )
    (net (code "95") (name "Net-(U8D-IN4+)") (class "Default")
      (node (ref "R25") (pin "1") (pinfunction "1_1") (pintype "passive"))
      (node (ref "R26") (pin "2") (pinfunction "2_2") (pintype "passive"))
      (node (ref "U8") (pin "11") (pinfunction "IN4+_11") (pintype "input"))
    )
    (net (code "96") (name "Net-(U9-ANODE(+))") (class "Default")
      (node (ref "R53") (pin "1") (pinfunction "1_1") (pintype "passive"))
      (node (ref "U9") (pin "1") (pinfunction "ANODE(+)_1") (pintype "passive"))
    )
    (net (code "97") (name "Net-(U10-Cfod)") (class "Default")
      (node (ref "C65") (pin "1") (pinfunction "1_1") (pintype "passive"))
      (node (ref "U10") (pin "7") (pinfunction "Cfod_7") (pintype "passive"))
    )
    (net (code "98") (name "Net-(U10-Csc)") (class "Default")
      (node (ref "C64") (pin "1") (pinfunction "1_1") (pintype "passive"))
      (node (ref "R62") (pin "2") (pinfunction "2_2") (pintype "passive"))
      (node (ref "U10") (pin "8") (pinfunction "Csc_8") (pintype "passive"))
    )
    (net (code "99") (name "Net-(U10-Nu)") (class "Default")
      (node (ref "C62") (pin "1") (pinfunction "1_1") (pintype "passive"))
      (node (ref "R61") (pin "1") (pinfunction "1_1") (pintype "passive"))
      (node (ref "R62") (pin "1") (pinfunction "1_1") (pintype "passive"))
      (node (ref "U10") (pin "21") (pinfunction "Nu_21") (pintype "passive"))
      (node (ref "U10") (pin "22") (pinfunction "Nv_22") (pintype "passive"))
      (node (ref "U10") (pin "23") (pinfunction "Nw_23") (pintype "passive"))
    )
    (net (code "100") (name "Net-(U11-40)") (class "Default")
      (node (ref "C51") (pin "1") (pinfunction "1_1") (pintype "passive"))
      (node (ref "R52") (pin "2") (pinfunction "2_2") (pintype "passive"))
      (node (ref "U11") (pin "2") (pinfunction "40_2") (pintype "passive"))
    )
    (net (code "101") (name "Net-(U12-IN1)") (class "Default")
      (node (ref "R41") (pin "2") (pinfunction "2_2") (pintype "passive"))
      (node (ref "U12") (pin "1") (pinfunction "IN1_1") (pintype "passive"))
      (node (ref "U8") (pin "13") (pinfunction "OUT4_13") (pintype "output"))
    )
    (net (code "102") (name "Net-(U12-IN2)") (class "Default")
      (node (ref "R44") (pin "2") (pinfunction "2_2") (pintype "passive"))
      (node (ref "U12") (pin "2") (pinfunction "IN2_2") (pintype "passive"))
      (node (ref "U12") (pin "5") (pinfunction "IN5_5") (pintype "passive"))
      (node (ref "U8") (pin "14") (pinfunction "OUT3_14") (pintype "output"))
    )
    (net (code "103") (name "Net-(U12-IN3)") (class "Default")
      (node (ref "R46") (pin "2") (pinfunction "2_2") (pintype "passive"))
      (node (ref "U12") (pin "3") (pinfunction "IN3_3") (pintype "passive"))
      (node (ref "U8") (pin "1") (pinfunction "OUT2_1") (pintype "output"))
    )
    (net (code "104") (name "Net-(U12-IN4)") (class "Default")
      (node (ref "R50") (pin "2") (pinfunction "2_2") (pintype "passive"))
      (node (ref "U12") (pin "4") (pinfunction "IN4_4") (pintype "passive"))
      (node (ref "U12") (pin "6") (pinfunction "IN6_6") (pintype "passive"))
      (node (ref "U8") (pin "2") (pinfunction "OUT1_2") (pintype "output"))
    )
    (net (code "105") (name "Net-(U12-OUT1)") (class "Default")
      (node (ref "U12") (pin "16") (pinfunction "OUT1_16") (pintype "passive"))
      (node (ref "U20") (pin "2") (pinfunction "2_2") (pintype "passive"))
    )
    (net (code "106") (name "Net-(U12-OUT2)") (class "Default")
      (node (ref "U12") (pin "15") (pinfunction "OUT2_15") (pintype "passive"))
      (node (ref "U18") (pin "2") (pinfunction "2_2") (pintype "passive"))
    )
    (net (code "107") (name "Net-(U12-OUT3)") (class "Default")
      (node (ref "U12") (pin "14") (pinfunction "OUT3_14") (pintype "passive"))
      (node (ref "U17") (pin "2") (pinfunction "2_2") (pintype "passive"))
    )
    (net (code "108") (name "Net-(U12-OUT4)") (class "Default")
      (node (ref "U12") (pin "13") (pinfunction "OUT4_13") (pintype "passive"))
      (node (ref "U16") (pin "2") (pinfunction "2_2") (pintype "passive"))
    )
    (net (code "109") (name "Net-(U12-OUT5)") (class "Default")
      (node (ref "U12") (pin "12") (pinfunction "OUT5_12") (pintype "passive"))
      (node (ref "U9") (pin "3") (pinfunction "CATHODE(-)_3") (pintype "passive"))
    )
    (net (code "110") (name "Net-(U12-OUT8)") (class "Default")
      (node (ref "K1") (pin "5") (pinfunction "5_5") (pintype "passive"))
      (node (ref "U12") (pin "11") (pinfunction "OUT8_11") (pintype "passive"))
    )
    (net (code "111") (name "Net-(U13-ANODE(+))") (class "Default")
      (node (ref "P3") (pin "12") (pinfunction "12_12") (pintype "passive"))
      (node (ref "U13") (pin "1") (pinfunction "ANODE(+)_1") (pintype "passive"))
      (node (ref "U15") (pin "3") (pinfunction "CATHODE(-)_3") (pintype "passive"))
    )
    (net (code "112") (name "Net-(U13-CATHODE(-))") (class "Default")
      (node (ref "P3") (pin "6") (pinfunction "6_6") (pintype "passive"))
      (node (ref "U13") (pin "3") (pinfunction "CATHODE(-)_3") (pintype "passive"))
      (node (ref "U15") (pin "1") (pinfunction "ANODE(+)_1") (pintype "passive"))
    )
    (net (code "113") (name "Net-(U14-40)") (class "Default")
      (node (ref "C63") (pin "1") (pinfunction "1_1") (pintype "passive"))
      (node (ref "R58") (pin "2") (pinfunction "2_2") (pintype "passive"))
      (node (ref "U14") (pin "2") (pinfunction "40_2") (pintype "passive"))
    )
    (net (code "114") (name "Net-(U19-ANODE(+))") (class "Default")
      (node (ref "P3") (pin "10") (pinfunction "10_10") (pintype "passive"))
      (node (ref "U19") (pin "1") (pinfunction "ANODE(+)_1") (pintype "passive"))
      (node (ref "U21") (pin "3") (pinfunction "CATHODE(-)_3") (pintype "passive"))
    )
    (net (code "115") (name "Net-(U19-CATHODE(-))") (class "Default")
      (node (ref "P3") (pin "4") (pinfunction "4_4") (pintype "passive"))
      (node (ref "U19") (pin "3") (pinfunction "CATHODE(-)_3") (pintype "passive"))
      (node (ref "U21") (pin "1") (pinfunction "ANODE(+)_1") (pintype "passive"))
    )
    (net (code "116") (name "Net-(U22-ANODE(+))") (class "Default")
      (node (ref "P3") (pin "8") (pinfunction "8_8") (pintype "passive"))
      (node (ref "U22") (pin "1") (pinfunction "ANODE(+)_1") (pintype "passive"))
      (node (ref "U24") (pin "3") (pinfunction "CATHODE(-)_3") (pintype "passive"))
    )
    (net (code "117") (name "Net-(U22-CATHODE(-))") (class "Default")
      (node (ref "P3") (pin "2") (pinfunction "2_2") (pintype "passive"))
      (node (ref "U22") (pin "3") (pinfunction "CATHODE(-)_3") (pintype "passive"))
      (node (ref "U24") (pin "1") (pinfunction "ANODE(+)_1") (pintype "passive"))
    )
    (net (code "118") (name "Net-(U23-A)") (class "Default")
      (node (ref "R63") (pin "1") (pinfunction "1_1") (pintype "passive"))
      (node (ref "U23") (pin "1") (pinfunction "A_1") (pintype "passive"))
    )
    (net (code "119") (name "unconnected-(T1-NC-Pad6)") (class "Default")
      (node (ref "T1") (pin "6") (pinfunction "NC_6") (pintype "passive"))
    )
    (net (code "120") (name "unconnected-(T1-NC-Pad9)") (class "Default")
      (node (ref "T1") (pin "9") (pinfunction "NC_9") (pintype "passive"))
    )
    (net (code "121") (name "unconnected-(T1-VS--Pad2)") (class "Default")
      (node (ref "T1") (pin "2") (pinfunction "VS-_2") (pintype "passive"))
    )
    (net (code "122") (name "unconnected-(U4-NC-Pad4)") (class "Default")
      (node (ref "U4") (pin "4") (pinfunction "NC_4") (pintype "passive"))
    )
    (net (code "123") (name "unconnected-(U4-NC-Pad5)") (class "Default")
      (node (ref "U4") (pin "5") (pinfunction "NC_5") (pintype "passive"))
    )
    (net (code "124") (name "unconnected-(U7-NC-Pad4)") (class "Default")
      (node (ref "U7") (pin "4") (pinfunction "NC_4") (pintype "passive"))
    )
    (net (code "125") (name "unconnected-(U7-NC-Pad5)") (class "Default")
      (node (ref "U7") (pin "5") (pinfunction "NC_5") (pintype "passive"))
    )
    (net (code "126") (name "unconnected-(U9-NC-Pad2)") (class "Default")
      (node (ref "U9") (pin "2") (pinfunction "NC_2") (pintype "passive"))
    )
    (net (code "127") (name "unconnected-(U12-D-Pad9)") (class "Default")
      (node (ref "U12") (pin "9") (pinfunction "D_9") (pintype "passive"))
    )
    (net (code "128") (name "unconnected-(U12-IN7-Pad7)") (class "Default")
      (node (ref "U12") (pin "7") (pinfunction "IN7_7") (pintype "passive"))
    )
    (net (code "129") (name "unconnected-(U12-OUT7-Pad10)") (class "Default")
      (node (ref "U12") (pin "10") (pinfunction "OUT7_10") (pintype "passive"))
    )
    (net (code "130") (name "unconnected-(U13-NC-Pad2)") (class "Default")
      (node (ref "U13") (pin "2") (pinfunction "NC_2") (pintype "passive"))
    )
    (net (code "131") (name "unconnected-(U15-NC-Pad2)") (class "Default")
      (node (ref "U15") (pin "2") (pinfunction "NC_2") (pintype "passive"))
    )
    (net (code "132") (name "unconnected-(U19-NC-Pad2)") (class "Default")
      (node (ref "U19") (pin "2") (pinfunction "NC_2") (pintype "passive"))
    )
    (net (code "133") (name "unconnected-(U21-NC-Pad2)") (class "Default")
      (node (ref "U21") (pin "2") (pinfunction "NC_2") (pintype "passive"))
    )
    (net (code "134") (name "unconnected-(U22-NC-Pad2)") (class "Default")
      (node (ref "U22") (pin "2") (pinfunction "NC_2") (pintype "passive"))
    )
    (net (code "135") (name "unconnected-(U24-NC-Pad2)") (class "Default")
      (node (ref "U24") (pin "2") (pinfunction "NC_2") (pintype "passive"))
    )
  )
)
